# WaldoRevC.net
KiCad netlist of a schematic drawn in EAGLE
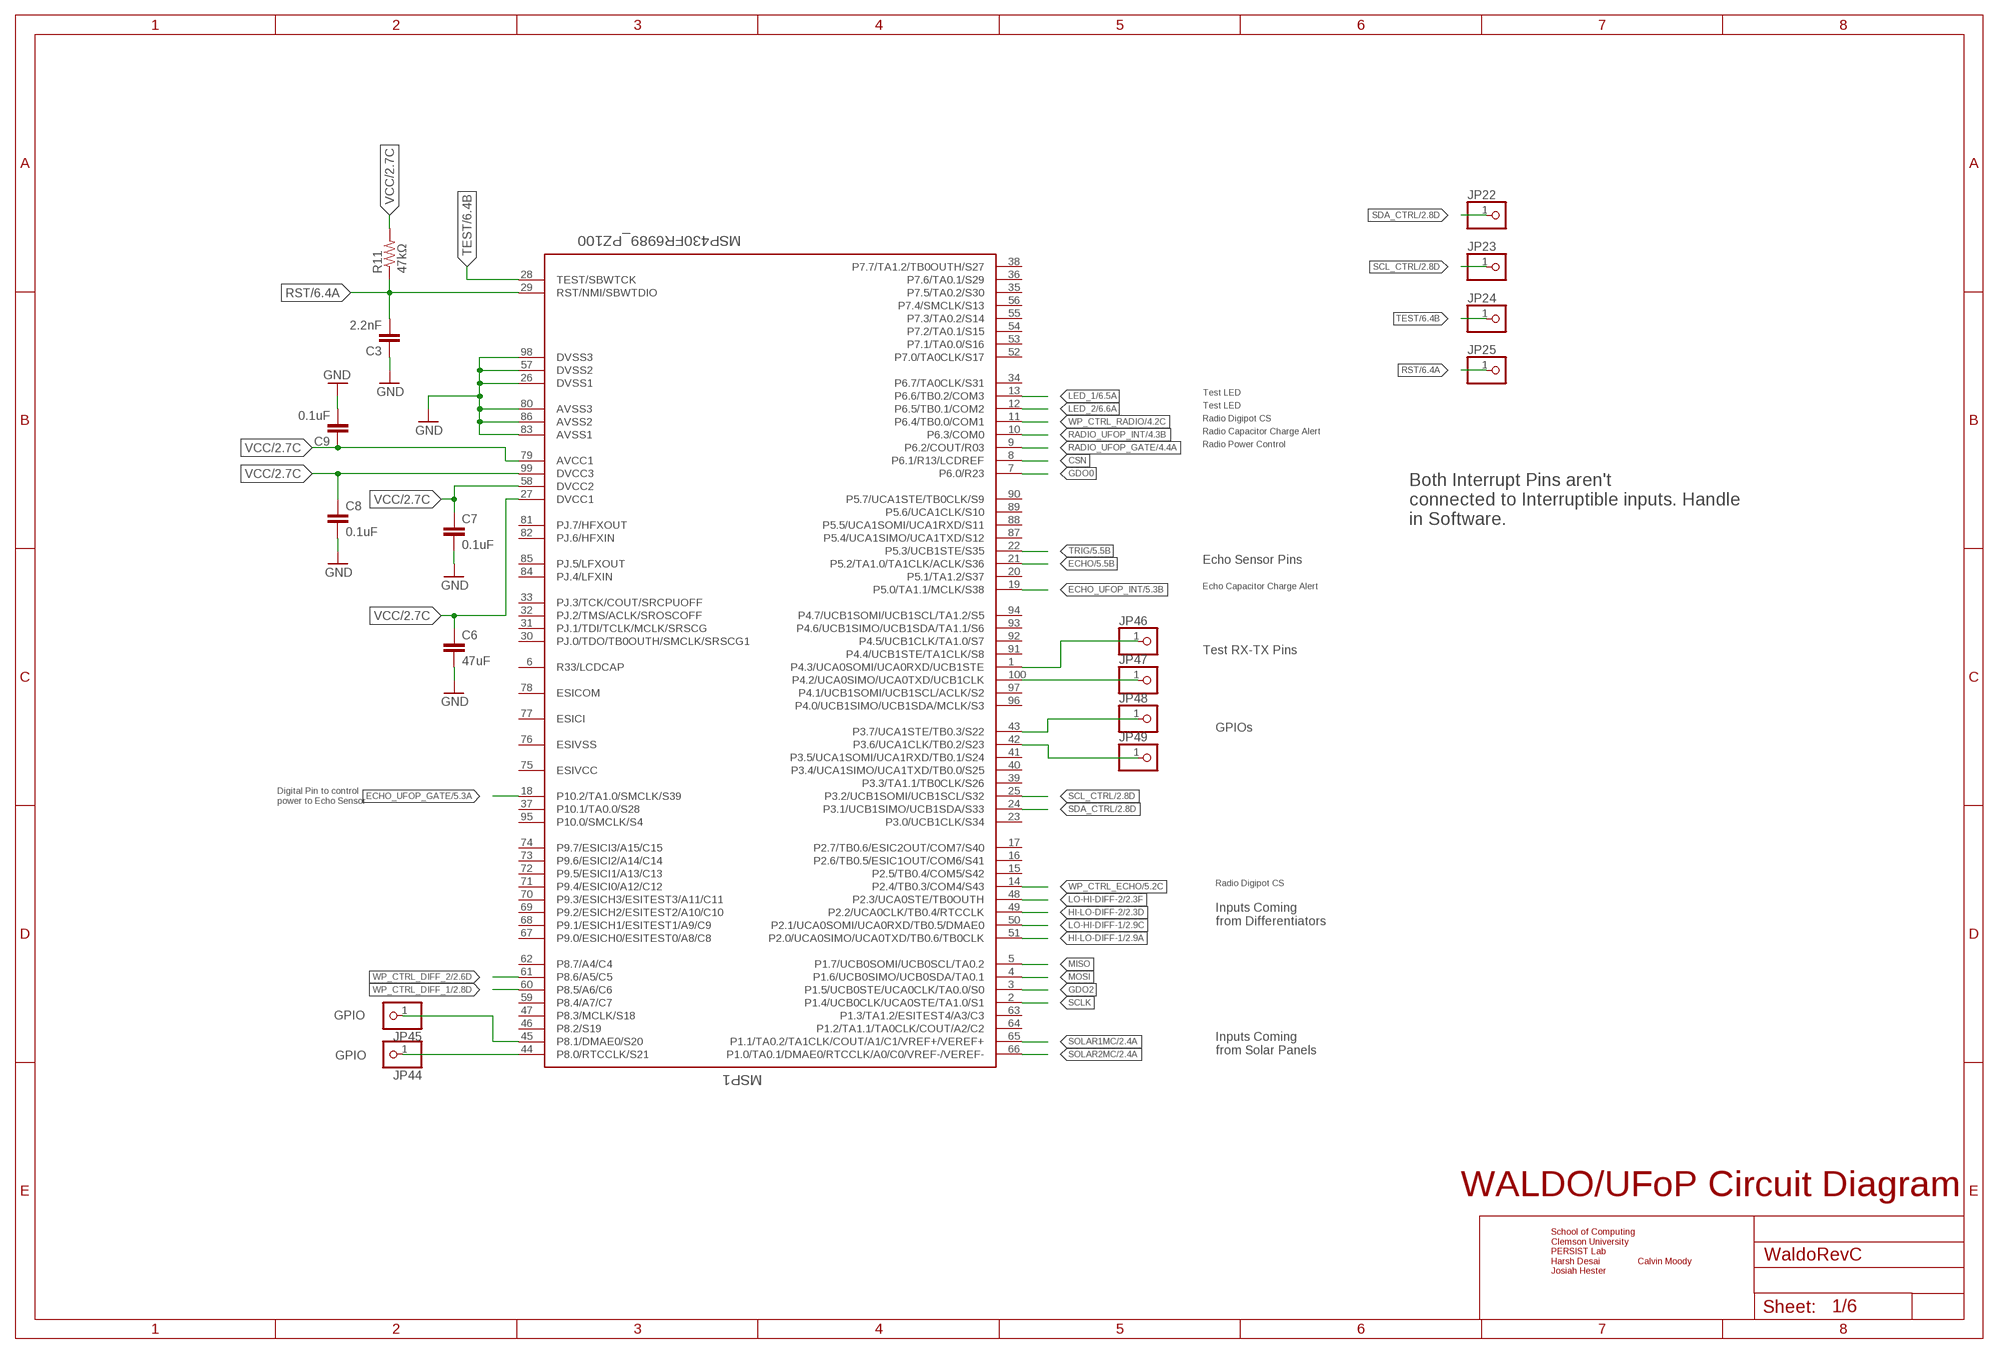
[diagram p0: schematic, sheet 1]
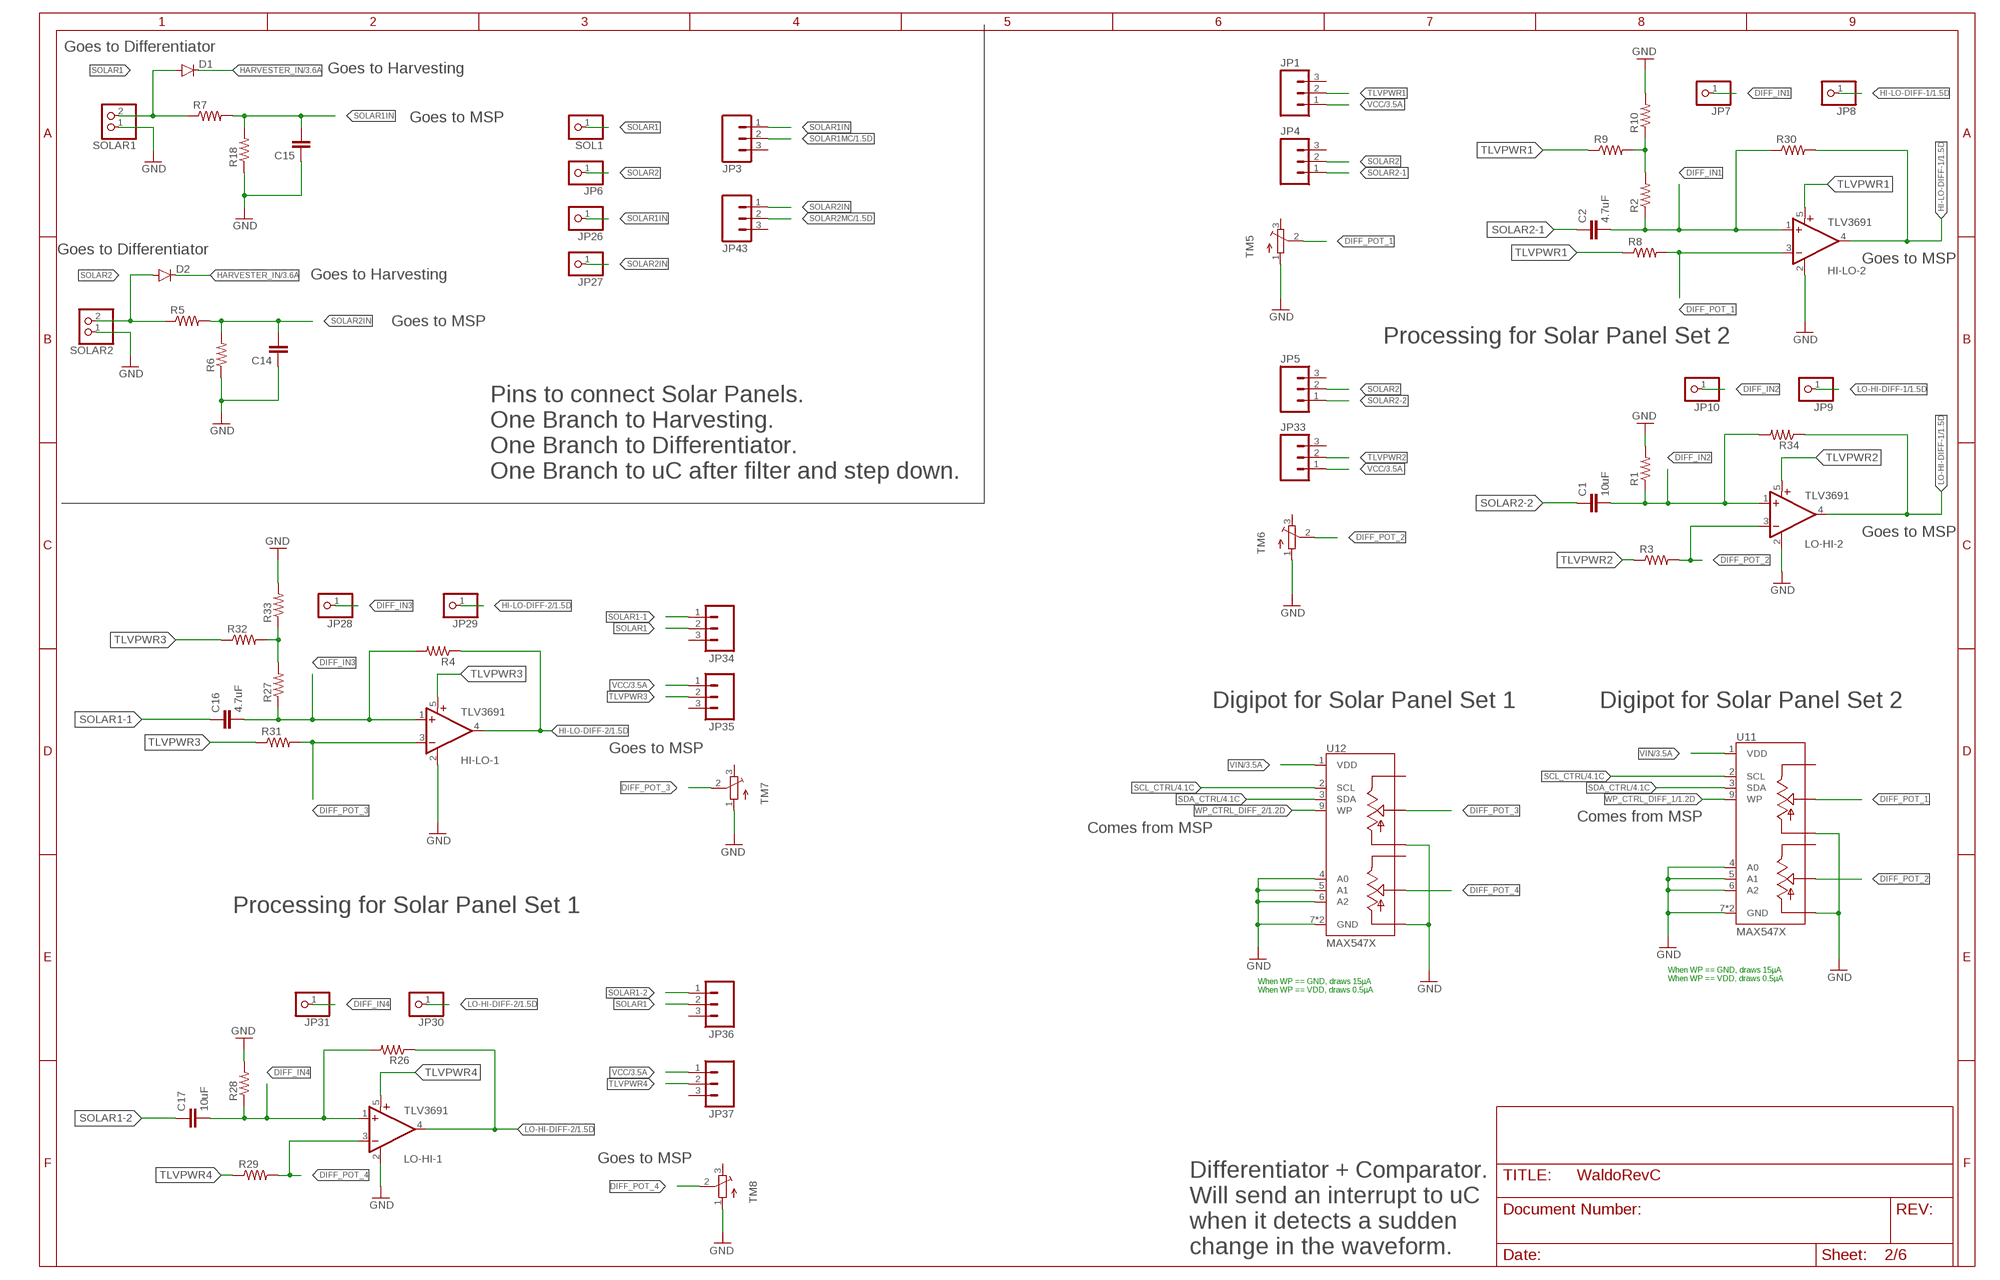
[diagram p1: schematic, sheet 2]
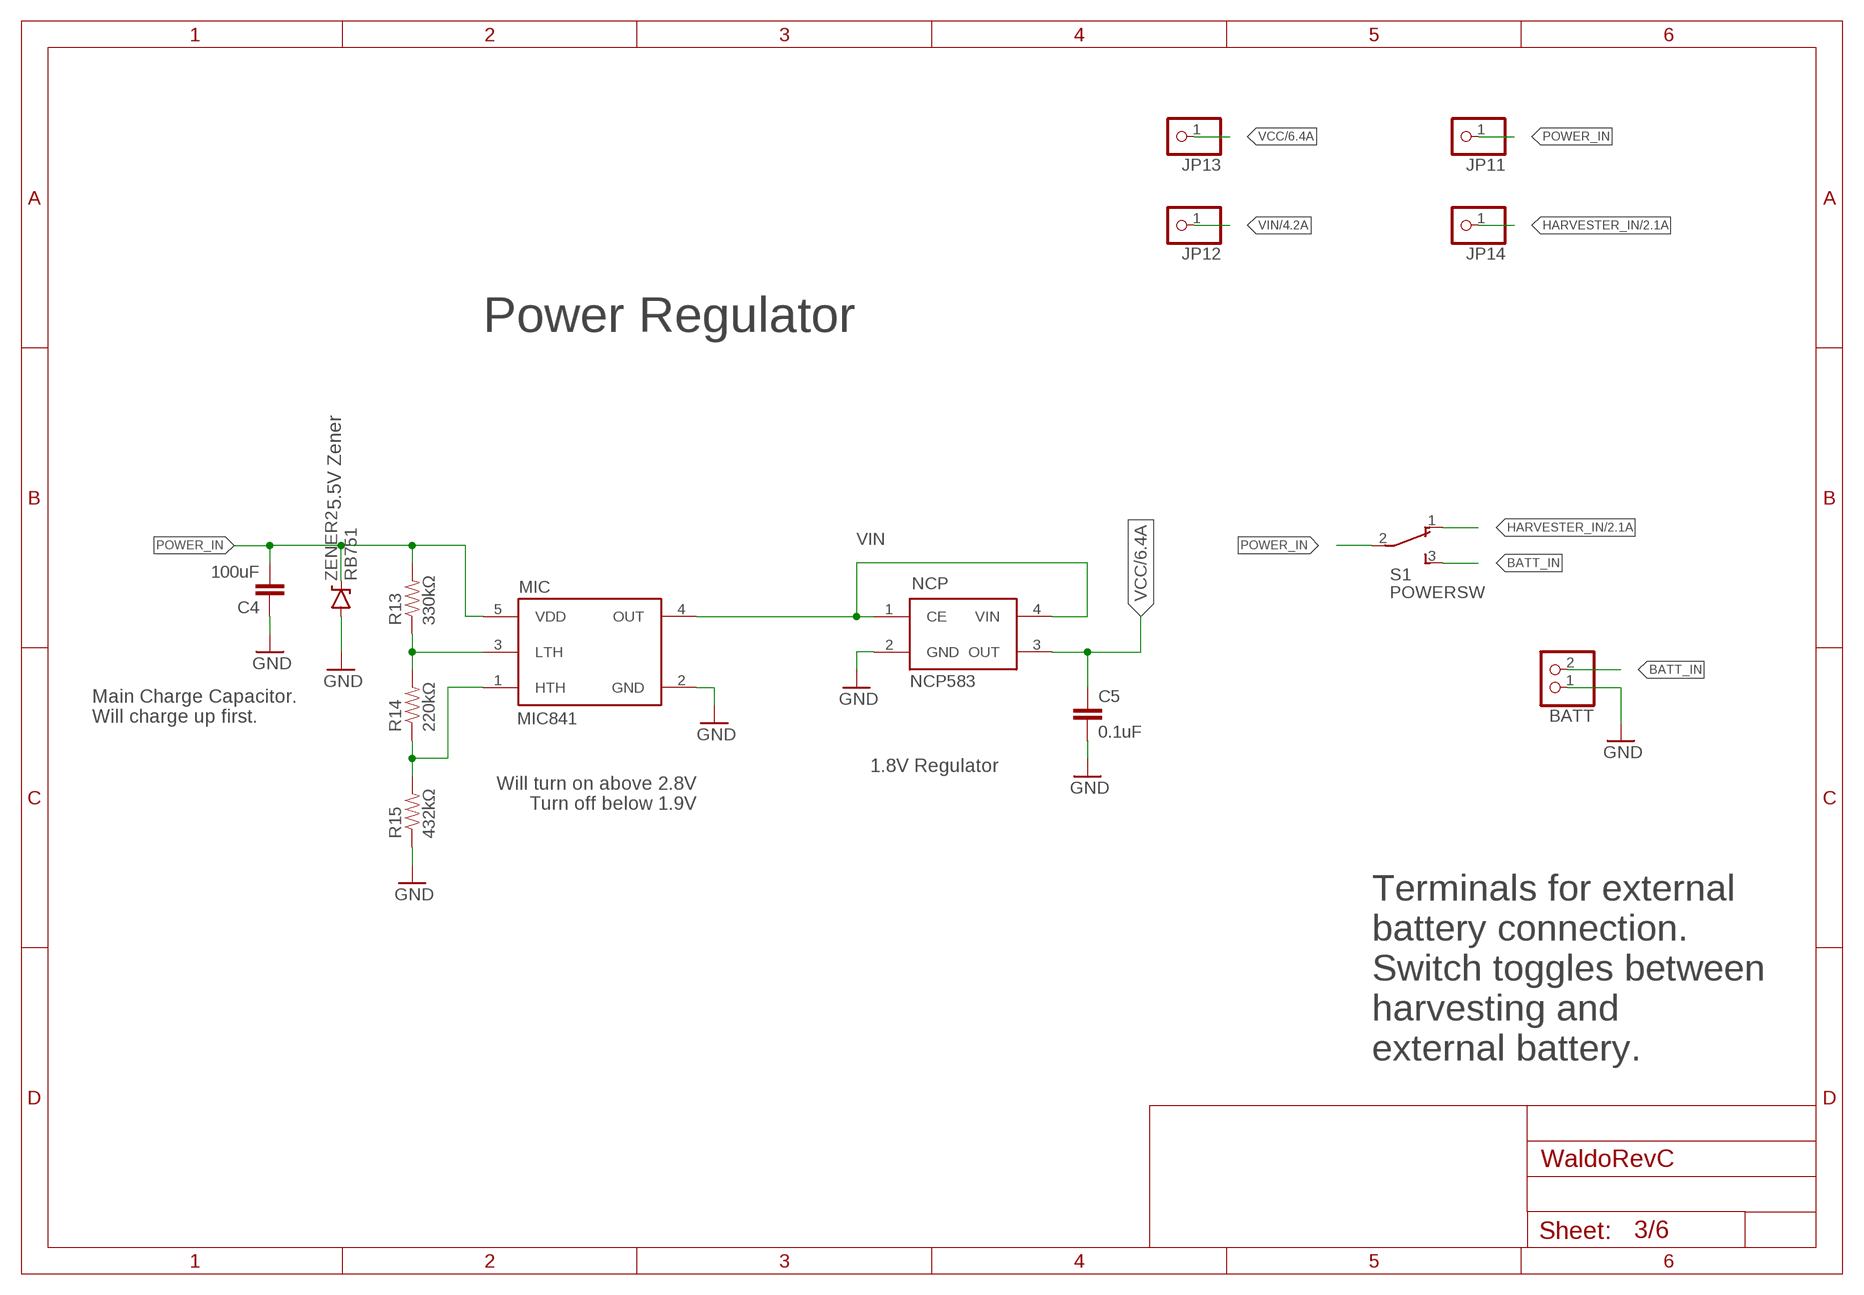
[diagram p2: schematic, sheet 3]
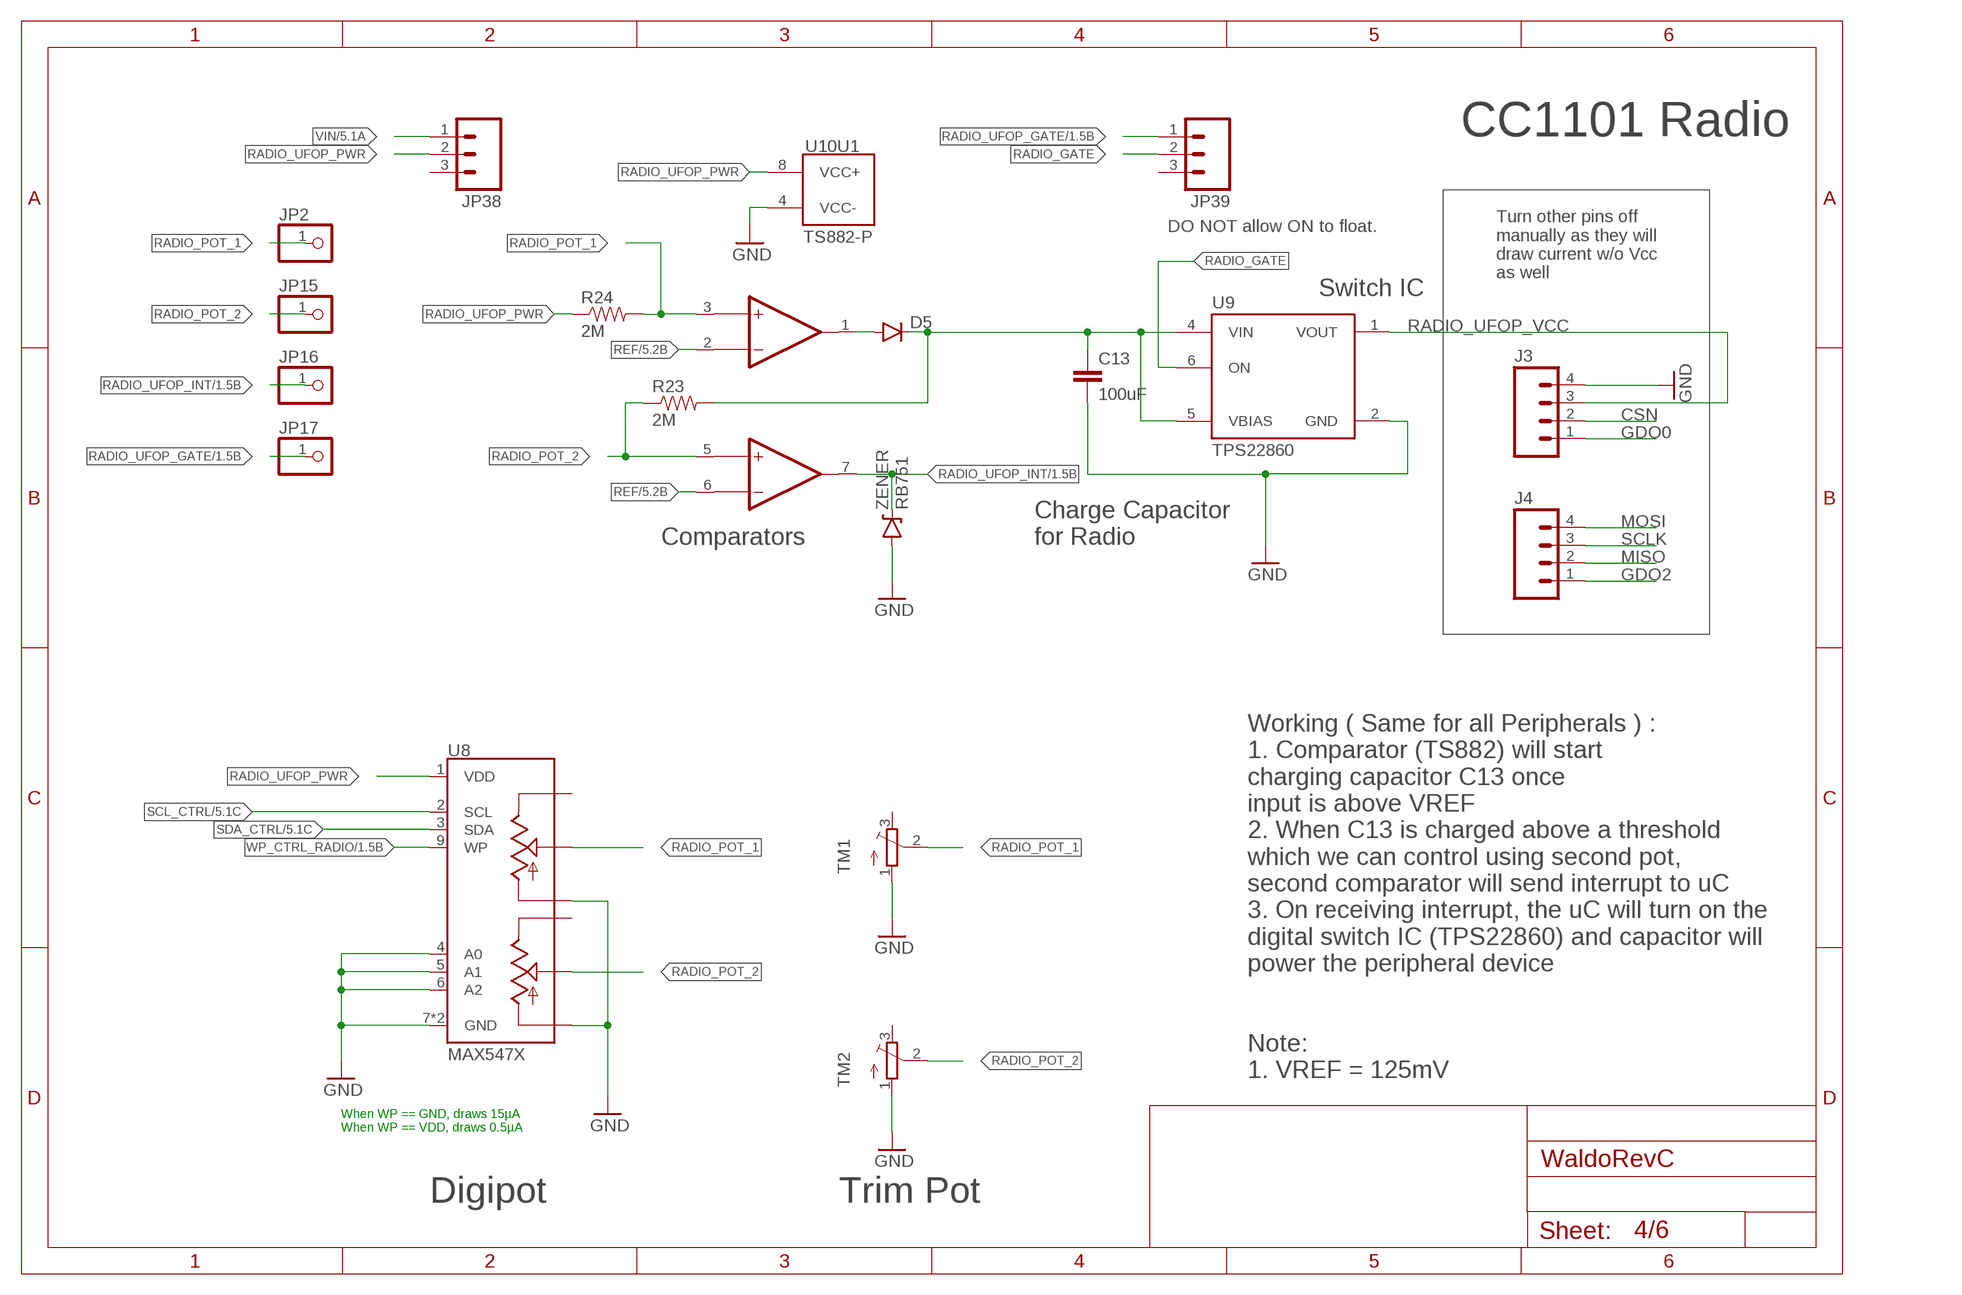
[diagram p3: schematic, sheet 4]
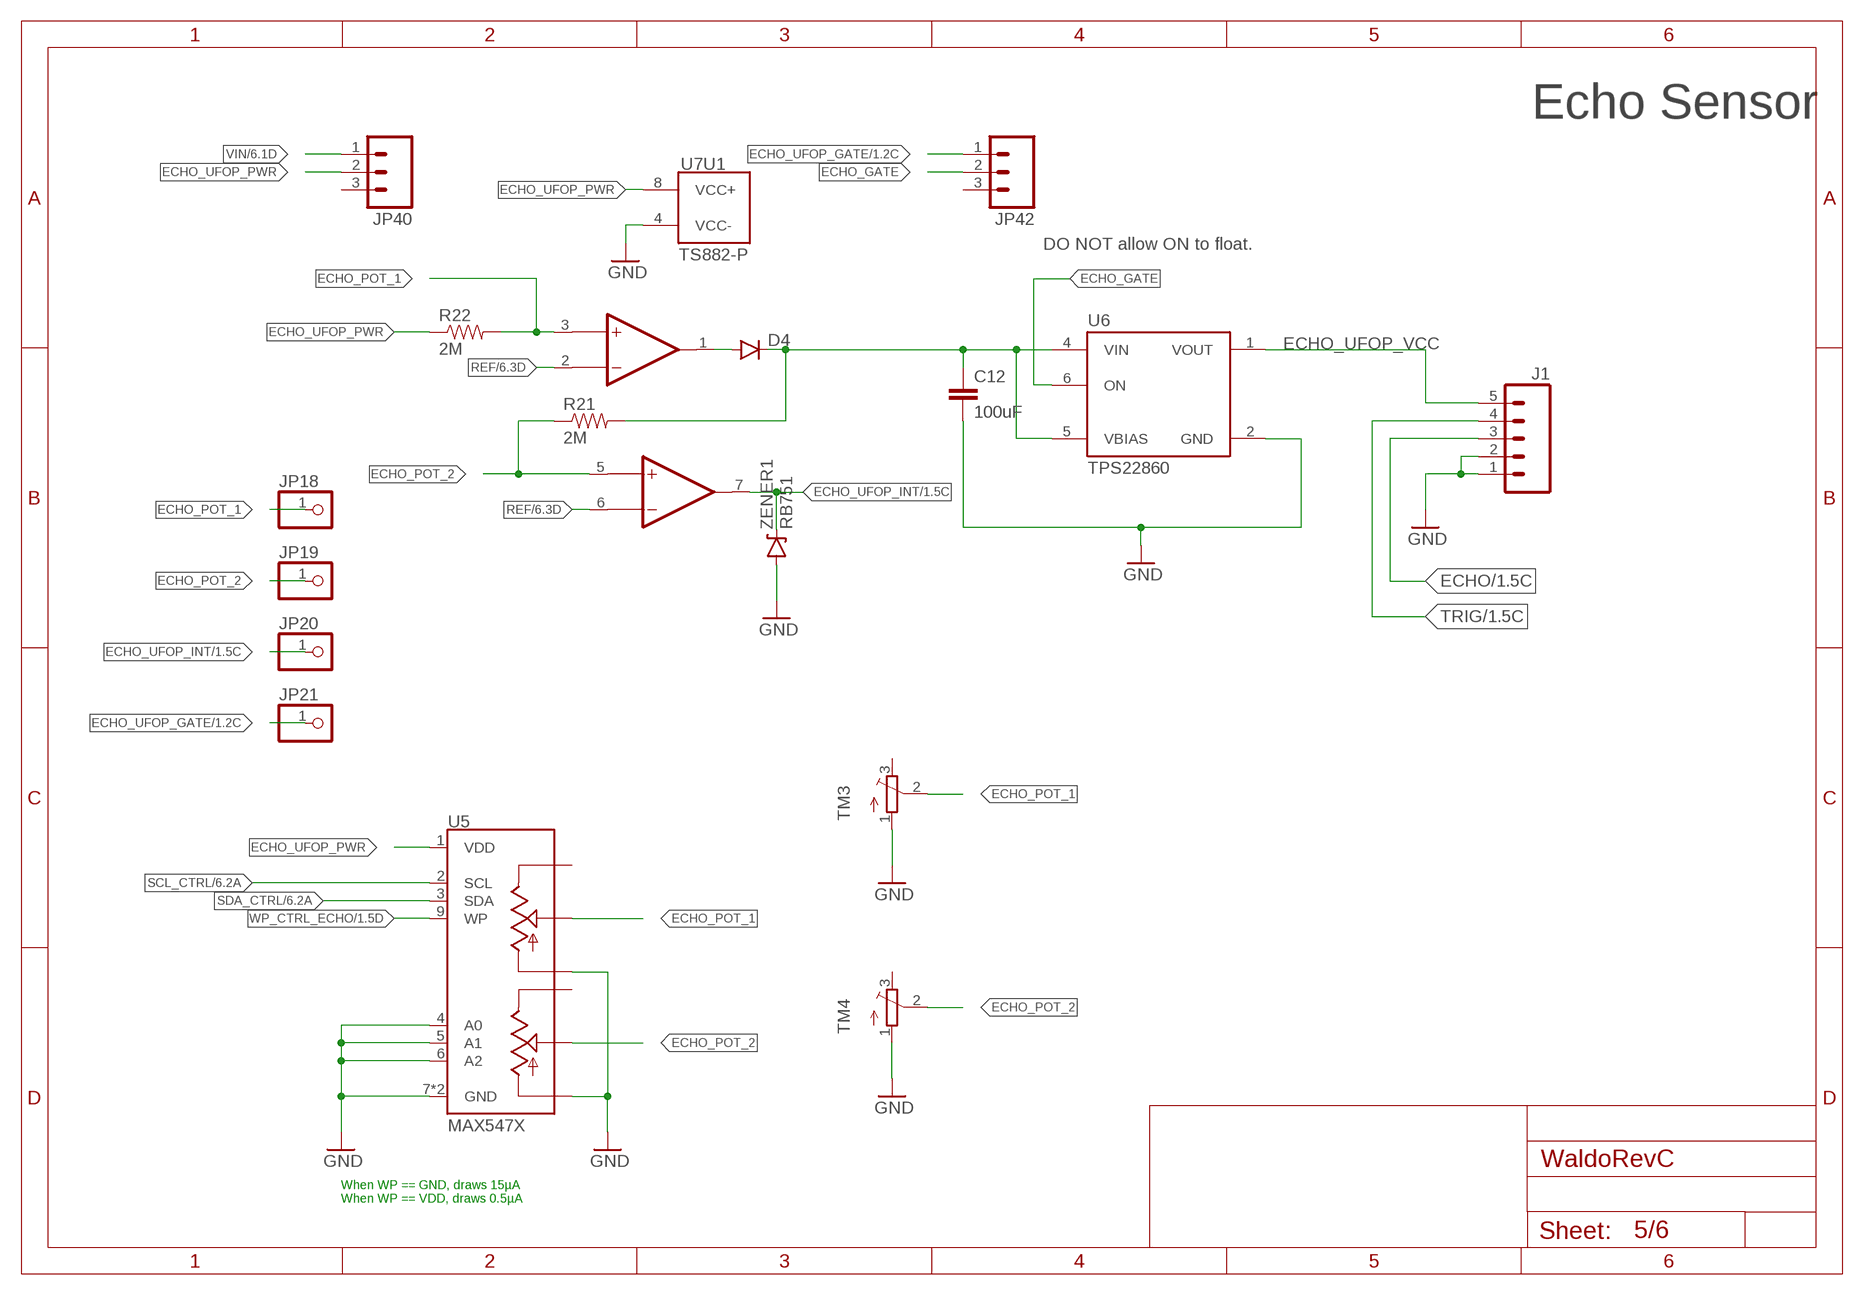
[diagram p4: schematic, sheet 5]
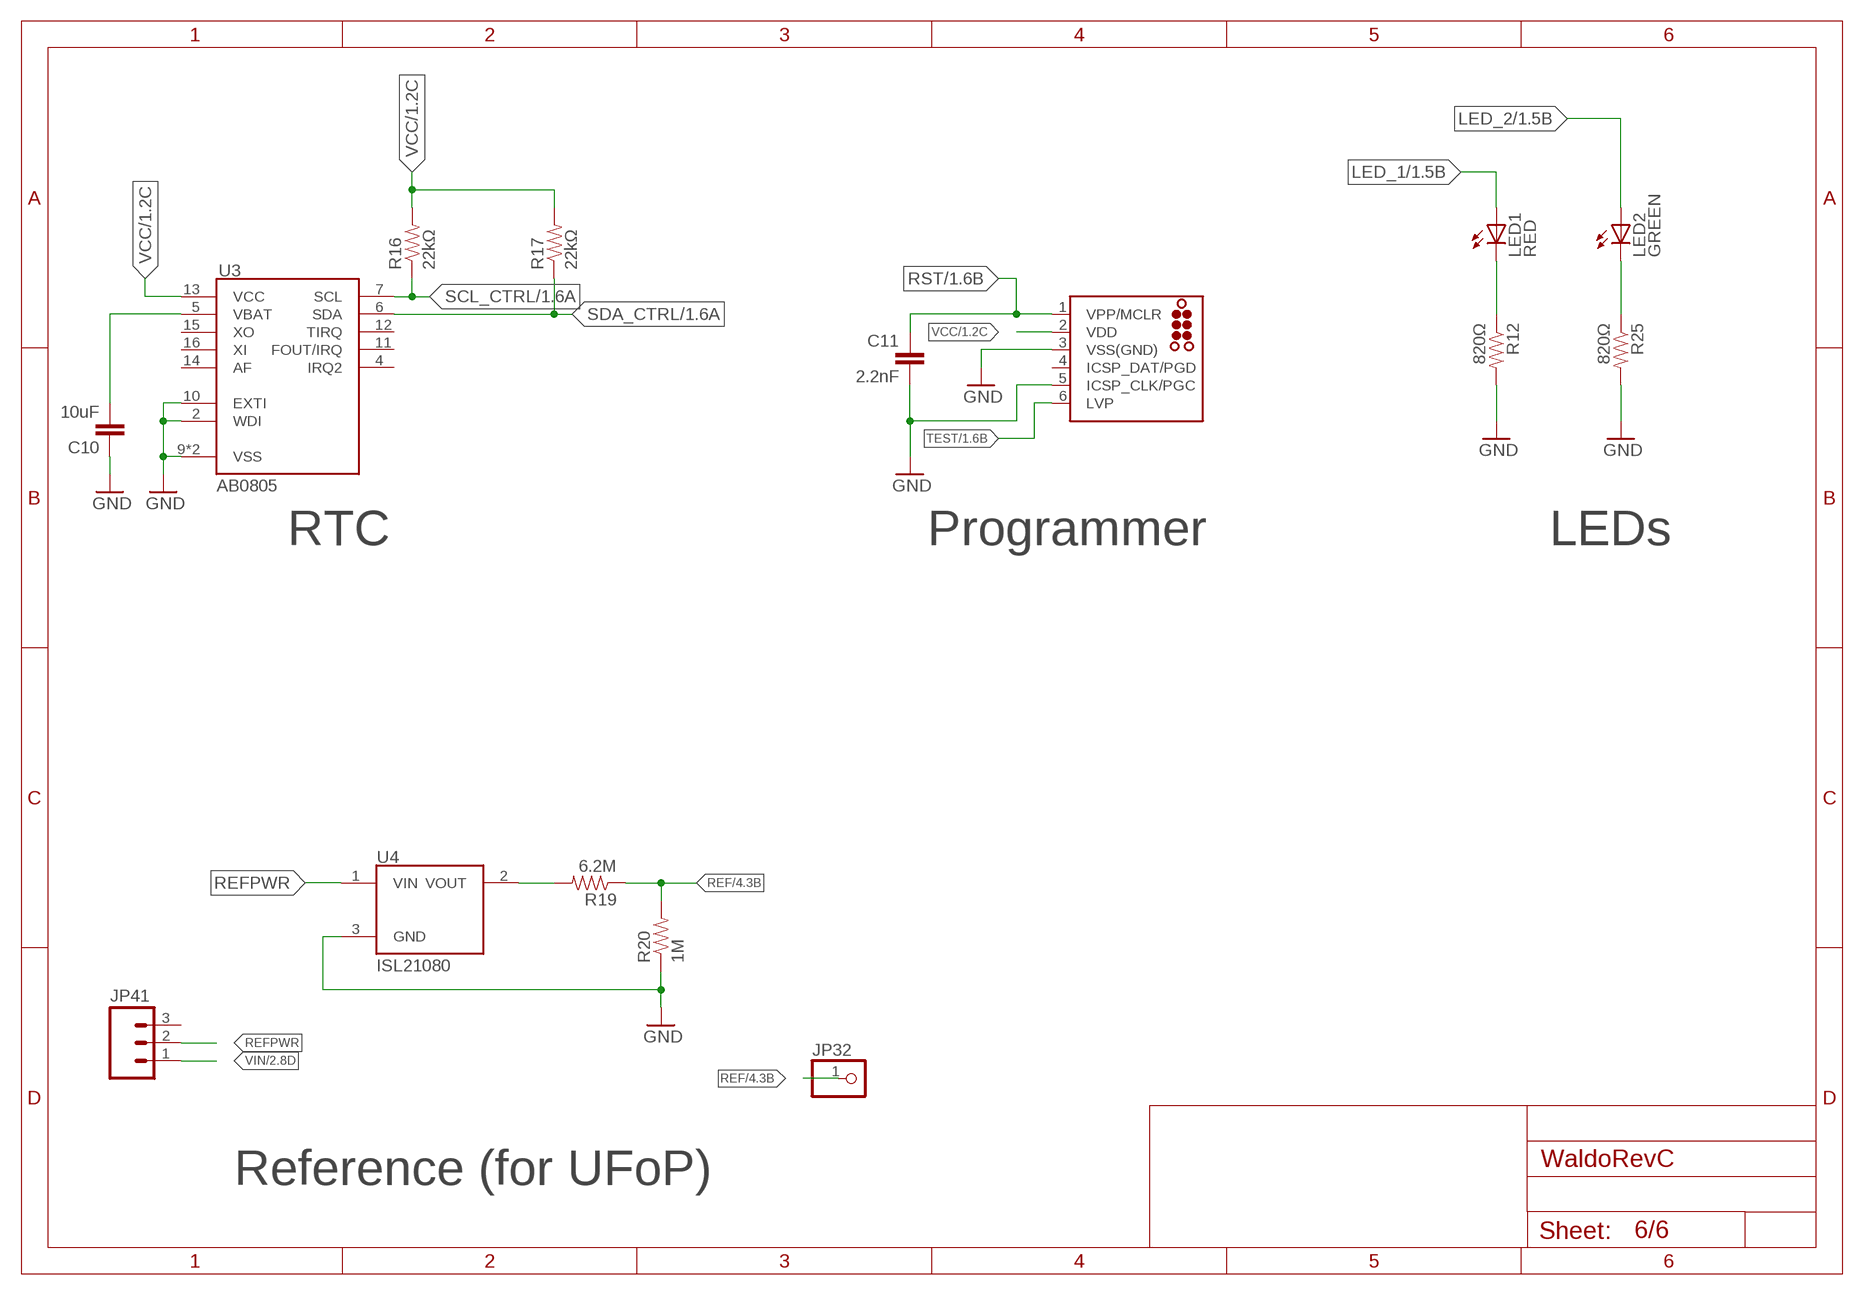
[diagram p5: schematic, sheet 6]

(export (version "E")
  (design (tool "Eeschema 10.0.6"))
  (components
    (comp (ref "C12")
      (value "100uF")
      (footprint "eagle-import:0805")
      (libsource (lib "eagle-import") (part "CAP0805"))
    )
    (comp (ref "D4")
      (value "DIODESOD523")
      (footprint "eagle-import:SOD523")
      (libsource (lib "eagle-import") (part "DIODESOD523"))
    )
    (comp (ref "J1")
      (value "M05PTH")
      (footprint "eagle-import:1X05")
      (libsource (lib "eagle-import") (part "M05PTH"))
    )
    (comp (ref "JP18")
      (value "PINHD-1X1")
      (footprint "eagle-import:1X01")
      (libsource (lib "eagle-import") (part "PINHD-1X1"))
    )
    (comp (ref "JP19")
      (value "PINHD-1X1")
      (footprint "eagle-import:1X01")
      (libsource (lib "eagle-import") (part "PINHD-1X1"))
    )
    (comp (ref "JP20")
      (value "PINHD-1X1")
      (footprint "eagle-import:1X01")
      (libsource (lib "eagle-import") (part "PINHD-1X1"))
    )
    (comp (ref "JP21")
      (value "PINHD-1X1")
      (footprint "eagle-import:1X01")
      (libsource (lib "eagle-import") (part "PINHD-1X1"))
    )
    (comp (ref "JP40")
      (value "M03")
      (footprint "eagle-import:1X03-1.27MM")
      (libsource (lib "eagle-import") (part "M03"))
    )
    (comp (ref "JP42")
      (value "M03")
      (footprint "eagle-import:1X03-1.27MM")
      (libsource (lib "eagle-import") (part "M03"))
    )
    (comp (ref "R21")
      (value "2M")
      (footprint "eagle-import:0805")
      (libsource (lib "eagle-import") (part "RESISTOR0805-RES"))
    )
    (comp (ref "R22")
      (value "2M")
      (footprint "eagle-import:0805")
      (libsource (lib "eagle-import") (part "RESISTOR0805-RES"))
    )
    (comp (ref "TM3")
      (value "TRIMPOTTC33X")
      (footprint "eagle-import:TC33X")
      (libsource (lib "eagle-import") (part "TRIMPOTTC33X"))
    )
    (comp (ref "TM4")
      (value "TRIMPOTTC33X")
      (footprint "eagle-import:TC33X")
      (libsource (lib "eagle-import") (part "TRIMPOTTC33X"))
    )
    (comp (ref "U5")
      (value "MAX547X")
      (footprint "eagle-import:QFN16")
      (libsource (lib "eagle-import") (part "MAX547X"))
    )
    (comp (ref "U6")
      (value "TPS22860")
      (footprint "eagle-import:TSOT23-6")
      (libsource (lib "eagle-import") (part "TPS22860"))
    )
    (comp (ref "U7")
      (value "TS882-P")
      (footprint "eagle-import:UDFN8")
      (fields (field (name "DIGIKEY") "497-14073-1-ND"))
      (libsource (lib "eagle-import") (part "TS882-P"))
    )
    (comp (ref "ZENER1")
      (value "RB751")
      (footprint "eagle-import:SOD-523")
      (libsource (lib "eagle-import") (part "DIODE-ZENER"))
    )
    (comp (ref "C3")
      (value "2.2nF")
      (footprint "eagle-import:0805")
      (libsource (lib "eagle-import") (part "CAP0805"))
    )
    (comp (ref "C6")
      (value "47uF")
      (footprint "eagle-import:0805")
      (libsource (lib "eagle-import") (part "CAP0805"))
    )
    (comp (ref "C7")
      (value "0.1uF")
      (footprint "eagle-import:0805")
      (libsource (lib "eagle-import") (part "CAP0805"))
    )
    (comp (ref "C8")
      (value "0.1uF")
      (footprint "eagle-import:0805")
      (libsource (lib "eagle-import") (part "CAP0805"))
    )
    (comp (ref "C9")
      (value "0.1uF")
      (footprint "eagle-import:0805")
      (libsource (lib "eagle-import") (part "CAP0805"))
    )
    (comp (ref "JP22")
      (value "PINHD-1X1")
      (footprint "eagle-import:1X01")
      (libsource (lib "eagle-import") (part "PINHD-1X1"))
    )
    (comp (ref "JP23")
      (value "PINHD-1X1")
      (footprint "eagle-import:1X01")
      (libsource (lib "eagle-import") (part "PINHD-1X1"))
    )
    (comp (ref "JP24")
      (value "PINHD-1X1")
      (footprint "eagle-import:1X01")
      (libsource (lib "eagle-import") (part "PINHD-1X1"))
    )
    (comp (ref "JP25")
      (value "PINHD-1X1")
      (footprint "eagle-import:1X01")
      (libsource (lib "eagle-import") (part "PINHD-1X1"))
    )
    (comp (ref "JP44")
      (value "PINHD-1X1")
      (footprint "eagle-import:1X01")
      (libsource (lib "eagle-import") (part "PINHD-1X1"))
    )
    (comp (ref "JP45")
      (value "PINHD-1X1")
      (footprint "eagle-import:1X01")
      (libsource (lib "eagle-import") (part "PINHD-1X1"))
    )
    (comp (ref "JP46")
      (value "PINHD-1X1")
      (footprint "eagle-import:1X01")
      (libsource (lib "eagle-import") (part "PINHD-1X1"))
    )
    (comp (ref "JP47")
      (value "PINHD-1X1")
      (footprint "eagle-import:1X01")
      (libsource (lib "eagle-import") (part "PINHD-1X1"))
    )
    (comp (ref "JP48")
      (value "PINHD-1X1")
      (footprint "eagle-import:1X01")
      (libsource (lib "eagle-import") (part "PINHD-1X1"))
    )
    (comp (ref "JP49")
      (value "PINHD-1X1")
      (footprint "eagle-import:1X01")
      (libsource (lib "eagle-import") (part "PINHD-1X1"))
    )
    (comp (ref "MSP1")
      (value "MSP430FR6989_PZ100")
      (footprint "eagle-import:PZ100")
      (libsource (lib "eagle-import") (part "MSP430FR6989_PZ100"))
    )
    (comp (ref "R11")
      (value "47kΩ")
      (footprint "eagle-import:0805")
      (libsource (lib "eagle-import") (part "RESISTOR0805-RES"))
    )
    (comp (ref "C1")
      (value "10uF")
      (footprint "eagle-import:0805")
      (libsource (lib "eagle-import") (part "CAP0805"))
    )
    (comp (ref "C2")
      (value "4.7uF")
      (footprint "eagle-import:0805")
      (libsource (lib "eagle-import") (part "CAP0805"))
    )
    (comp (ref "C14")
      (value "CAP0805")
      (footprint "eagle-import:0805")
      (libsource (lib "eagle-import") (part "CAP0805"))
    )
    (comp (ref "C15")
      (value "CAP0805")
      (footprint "eagle-import:0805")
      (libsource (lib "eagle-import") (part "CAP0805"))
    )
    (comp (ref "C16")
      (value "4.7uF")
      (footprint "eagle-import:0805")
      (libsource (lib "eagle-import") (part "CAP0805"))
    )
    (comp (ref "C17")
      (value "10uF")
      (footprint "eagle-import:0805")
      (libsource (lib "eagle-import") (part "CAP0805"))
    )
    (comp (ref "D1")
      (value "DIODESOD523")
      (footprint "eagle-import:SOD523")
      (libsource (lib "eagle-import") (part "DIODESOD523"))
    )
    (comp (ref "D2")
      (value "DIODESOD523")
      (footprint "eagle-import:SOD523")
      (libsource (lib "eagle-import") (part "DIODESOD523"))
    )
    (comp (ref "HI-LO-1")
      (value "TLV3691")
      (footprint "eagle-import:SC70-5")
      (libsource (lib "eagle-import") (part "TLV3691"))
    )
    (comp (ref "HI-LO-2")
      (value "TLV3691")
      (footprint "eagle-import:SC70-5")
      (libsource (lib "eagle-import") (part "TLV3691"))
    )
    (comp (ref "JP1")
      (value "M03")
      (footprint "eagle-import:1X03-1.27MM")
      (libsource (lib "eagle-import") (part "M03"))
    )
    (comp (ref "JP3")
      (value "M03")
      (footprint "eagle-import:1X03-1.27MM")
      (libsource (lib "eagle-import") (part "M03"))
    )
    (comp (ref "JP4")
      (value "M03")
      (footprint "eagle-import:1X03-1.27MM")
      (libsource (lib "eagle-import") (part "M03"))
    )
    (comp (ref "JP5")
      (value "M03")
      (footprint "eagle-import:1X03-1.27MM")
      (libsource (lib "eagle-import") (part "M03"))
    )
    (comp (ref "JP6")
      (value "PINHD-1X1")
      (footprint "eagle-import:1X01")
      (libsource (lib "eagle-import") (part "PINHD-1X1"))
    )
    (comp (ref "JP7")
      (value "PINHD-1X1")
      (footprint "eagle-import:1X01")
      (libsource (lib "eagle-import") (part "PINHD-1X1"))
    )
    (comp (ref "JP8")
      (value "PINHD-1X1")
      (footprint "eagle-import:1X01")
      (libsource (lib "eagle-import") (part "PINHD-1X1"))
    )
    (comp (ref "JP9")
      (value "PINHD-1X1")
      (footprint "eagle-import:1X01")
      (libsource (lib "eagle-import") (part "PINHD-1X1"))
    )
    (comp (ref "JP10")
      (value "PINHD-1X1")
      (footprint "eagle-import:1X01")
      (libsource (lib "eagle-import") (part "PINHD-1X1"))
    )
    (comp (ref "JP26")
      (value "PINHD-1X1")
      (footprint "eagle-import:1X01")
      (libsource (lib "eagle-import") (part "PINHD-1X1"))
    )
    (comp (ref "JP27")
      (value "PINHD-1X1")
      (footprint "eagle-import:1X01")
      (libsource (lib "eagle-import") (part "PINHD-1X1"))
    )
    (comp (ref "JP28")
      (value "PINHD-1X1")
      (footprint "eagle-import:1X01")
      (libsource (lib "eagle-import") (part "PINHD-1X1"))
    )
    (comp (ref "JP29")
      (value "PINHD-1X1")
      (footprint "eagle-import:1X01")
      (libsource (lib "eagle-import") (part "PINHD-1X1"))
    )
    (comp (ref "JP30")
      (value "PINHD-1X1")
      (footprint "eagle-import:1X01")
      (libsource (lib "eagle-import") (part "PINHD-1X1"))
    )
    (comp (ref "JP31")
      (value "PINHD-1X1")
      (footprint "eagle-import:1X01")
      (libsource (lib "eagle-import") (part "PINHD-1X1"))
    )
    (comp (ref "JP33")
      (value "M03")
      (footprint "eagle-import:1X03-1.27MM")
      (libsource (lib "eagle-import") (part "M03"))
    )
    (comp (ref "JP34")
      (value "M03")
      (footprint "eagle-import:1X03-1.27MM")
      (libsource (lib "eagle-import") (part "M03"))
    )
    (comp (ref "JP35")
      (value "M03")
      (footprint "eagle-import:1X03-1.27MM")
      (libsource (lib "eagle-import") (part "M03"))
    )
    (comp (ref "JP36")
      (value "M03")
      (footprint "eagle-import:1X03-1.27MM")
      (libsource (lib "eagle-import") (part "M03"))
    )
    (comp (ref "JP37")
      (value "M03")
      (footprint "eagle-import:1X03-1.27MM")
      (libsource (lib "eagle-import") (part "M03"))
    )
    (comp (ref "JP43")
      (value "M03")
      (footprint "eagle-import:1X03-1.27MM")
      (libsource (lib "eagle-import") (part "M03"))
    )
    (comp (ref "LO-HI-1")
      (value "TLV3691")
      (footprint "eagle-import:SC70-5")
      (libsource (lib "eagle-import") (part "TLV3691"))
    )
    (comp (ref "LO-HI-2")
      (value "TLV3691")
      (footprint "eagle-import:SC70-5")
      (libsource (lib "eagle-import") (part "TLV3691"))
    )
    (comp (ref "R1")
      (value "RESISTOR0805-RES")
      (footprint "eagle-import:0805")
      (libsource (lib "eagle-import") (part "RESISTOR0805-RES"))
    )
    (comp (ref "R2")
      (value "RESISTOR0805-RES")
      (footprint "eagle-import:0805")
      (libsource (lib "eagle-import") (part "RESISTOR0805-RES"))
    )
    (comp (ref "R3")
      (value "RESISTOR0805-RES")
      (footprint "eagle-import:0805")
      (libsource (lib "eagle-import") (part "RESISTOR0805-RES"))
    )
    (comp (ref "R4")
      (value "RESISTOR0805-RES")
      (footprint "eagle-import:0805")
      (libsource (lib "eagle-import") (part "RESISTOR0805-RES"))
    )
    (comp (ref "R5")
      (value "RESISTOR0805-RES")
      (footprint "eagle-import:0805")
      (libsource (lib "eagle-import") (part "RESISTOR0805-RES"))
    )
    (comp (ref "R6")
      (value "RESISTOR0805-RES")
      (footprint "eagle-import:0805")
      (libsource (lib "eagle-import") (part "RESISTOR0805-RES"))
    )
    (comp (ref "R7")
      (value "RESISTOR0805-RES")
      (footprint "eagle-import:0805")
      (libsource (lib "eagle-import") (part "RESISTOR0805-RES"))
    )
    (comp (ref "R8")
      (value "RESISTOR0805-RES")
      (footprint "eagle-import:0805")
      (libsource (lib "eagle-import") (part "RESISTOR0805-RES"))
    )
    (comp (ref "R9")
      (value "RESISTOR0805-RES")
      (footprint "eagle-import:0805")
      (libsource (lib "eagle-import") (part "RESISTOR0805-RES"))
    )
    (comp (ref "R10")
      (value "RESISTOR0805-RES")
      (footprint "eagle-import:0805")
      (libsource (lib "eagle-import") (part "RESISTOR0805-RES"))
    )
    (comp (ref "R18")
      (value "RESISTOR0805-RES")
      (footprint "eagle-import:0805")
      (libsource (lib "eagle-import") (part "RESISTOR0805-RES"))
    )
    (comp (ref "R26")
      (value "RESISTOR0805-RES")
      (footprint "eagle-import:0805")
      (libsource (lib "eagle-import") (part "RESISTOR0805-RES"))
    )
    (comp (ref "R27")
      (value "RESISTOR0805-RES")
      (footprint "eagle-import:0805")
      (libsource (lib "eagle-import") (part "RESISTOR0805-RES"))
    )
    (comp (ref "R28")
      (value "RESISTOR0805-RES")
      (footprint "eagle-import:0805")
      (libsource (lib "eagle-import") (part "RESISTOR0805-RES"))
    )
    (comp (ref "R29")
      (value "RESISTOR0805-RES")
      (footprint "eagle-import:0805")
      (libsource (lib "eagle-import") (part "RESISTOR0805-RES"))
    )
    (comp (ref "R30")
      (value "RESISTOR0805-RES")
      (footprint "eagle-import:0805")
      (libsource (lib "eagle-import") (part "RESISTOR0805-RES"))
    )
    (comp (ref "R31")
      (value "RESISTOR0805-RES")
      (footprint "eagle-import:0805")
      (libsource (lib "eagle-import") (part "RESISTOR0805-RES"))
    )
    (comp (ref "R32")
      (value "RESISTOR0805-RES")
      (footprint "eagle-import:0805")
      (libsource (lib "eagle-import") (part "RESISTOR0805-RES"))
    )
    (comp (ref "R33")
      (value "RESISTOR0805-RES")
      (footprint "eagle-import:0805")
      (libsource (lib "eagle-import") (part "RESISTOR0805-RES"))
    )
    (comp (ref "R34")
      (value "RESISTOR0805-RES")
      (footprint "eagle-import:0805")
      (libsource (lib "eagle-import") (part "RESISTOR0805-RES"))
    )
    (comp (ref "SOL1")
      (value "PINHD-1X1")
      (footprint "eagle-import:1X01")
      (libsource (lib "eagle-import") (part "PINHD-1X1"))
    )
    (comp (ref "SOLAR1")
      (value "PINHD-1X2")
      (footprint "eagle-import:1X02")
      (libsource (lib "eagle-import") (part "PINHD-1X2"))
    )
    (comp (ref "SOLAR2")
      (value "PINHD-1X2")
      (footprint "eagle-import:1X02")
      (libsource (lib "eagle-import") (part "PINHD-1X2"))
    )
    (comp (ref "TM5")
      (value "TRIMPOTTC33X")
      (footprint "eagle-import:TC33X")
      (libsource (lib "eagle-import") (part "TRIMPOTTC33X"))
    )
    (comp (ref "TM6")
      (value "TRIMPOTTC33X")
      (footprint "eagle-import:TC33X")
      (libsource (lib "eagle-import") (part "TRIMPOTTC33X"))
    )
    (comp (ref "TM7")
      (value "TRIMPOTTC33X")
      (footprint "eagle-import:TC33X")
      (libsource (lib "eagle-import") (part "TRIMPOTTC33X"))
    )
    (comp (ref "TM8")
      (value "TRIMPOTTC33X")
      (footprint "eagle-import:TC33X")
      (libsource (lib "eagle-import") (part "TRIMPOTTC33X"))
    )
    (comp (ref "U11")
      (value "MAX547X")
      (footprint "eagle-import:QFN16")
      (libsource (lib "eagle-import") (part "MAX547X"))
    )
    (comp (ref "U12")
      (value "MAX547X")
      (footprint "eagle-import:QFN16")
      (libsource (lib "eagle-import") (part "MAX547X"))
    )
    (comp (ref "C10")
      (value "10uF")
      (footprint "eagle-import:0805")
      (libsource (lib "eagle-import") (part "CAP0805"))
    )
    (comp (ref "C11")
      (value "2.2nF")
      (footprint "eagle-import:0805")
      (libsource (lib "eagle-import") (part "CAP0805"))
    )
    (comp (ref "J2")
      (value "TC2030-MCP-NL")
      (footprint "eagle-import:TC2030-MCP-NL")
      (libsource (lib "eagle-import") (part "TC2030-MCP-NL"))
    )
    (comp (ref "JP32")
      (value "PINHD-1X1")
      (footprint "eagle-import:1X01")
      (libsource (lib "eagle-import") (part "PINHD-1X1"))
    )
    (comp (ref "JP41")
      (value "M03")
      (footprint "eagle-import:1X03-1.27MM")
      (libsource (lib "eagle-import") (part "M03"))
    )
    (comp (ref "LED1")
      (value "RED")
      (footprint "eagle-import:CHIP-LED0805")
      (libsource (lib "eagle-import") (part "LEDCHIP-LED0805"))
    )
    (comp (ref "LED2")
      (value "GREEN")
      (footprint "eagle-import:CHIP-LED0805")
      (libsource (lib "eagle-import") (part "LEDCHIP-LED0805"))
    )
    (comp (ref "R12")
      (value "820Ω")
      (footprint "eagle-import:0805")
      (libsource (lib "eagle-import") (part "RESISTOR0805-RES"))
    )
    (comp (ref "R16")
      (value "22kΩ")
      (footprint "eagle-import:0805")
      (libsource (lib "eagle-import") (part "RESISTOR0805-RES"))
    )
    (comp (ref "R17")
      (value "22kΩ")
      (footprint "eagle-import:0805")
      (libsource (lib "eagle-import") (part "RESISTOR0805-RES"))
    )
    (comp (ref "R19")
      (value "6.2M")
      (footprint "eagle-import:0805")
      (libsource (lib "eagle-import") (part "RESISTOR0805-RES"))
    )
    (comp (ref "R20")
      (value "1M")
      (footprint "eagle-import:0805")
      (libsource (lib "eagle-import") (part "RESISTOR0805-RES"))
    )
    (comp (ref "R25")
      (value "820Ω")
      (footprint "eagle-import:0805")
      (libsource (lib "eagle-import") (part "RESISTOR0805-RES"))
    )
    (comp (ref "U3")
      (value "AB0805")
      (footprint "eagle-import:QFN16")
      (libsource (lib "eagle-import") (part "AB0805"))
    )
    (comp (ref "U4")
      (value "ISL21080")
      (footprint "eagle-import:SOT-23")
      (libsource (lib "eagle-import") (part "ISL21080"))
    )
    (comp (ref "BATT")
      (value "PINHD-1X2")
      (footprint "eagle-import:1X02")
      (libsource (lib "eagle-import") (part "PINHD-1X2"))
    )
    (comp (ref "C4")
      (value "100uF")
      (footprint "eagle-import:0805")
      (libsource (lib "eagle-import") (part "CAP0805"))
    )
    (comp (ref "C5")
      (value "0.1uF")
      (footprint "eagle-import:0805")
      (libsource (lib "eagle-import") (part "CAP0805"))
    )
    (comp (ref "JP11")
      (value "PINHD-1X1")
      (footprint "eagle-import:1X01")
      (libsource (lib "eagle-import") (part "PINHD-1X1"))
    )
    (comp (ref "JP12")
      (value "PINHD-1X1")
      (footprint "eagle-import:1X01")
      (libsource (lib "eagle-import") (part "PINHD-1X1"))
    )
    (comp (ref "JP13")
      (value "PINHD-1X1")
      (footprint "eagle-import:1X01")
      (libsource (lib "eagle-import") (part "PINHD-1X1"))
    )
    (comp (ref "JP14")
      (value "PINHD-1X1")
      (footprint "eagle-import:1X01")
      (libsource (lib "eagle-import") (part "PINHD-1X1"))
    )
    (comp (ref "MIC")
      (value "MIC841")
      (footprint "eagle-import:SC70-5")
      (libsource (lib "eagle-import") (part "MIC841"))
    )
    (comp (ref "NCP")
      (value "NCP583")
      (footprint "eagle-import:SC82-AB_1PRIMARY")
      (libsource (lib "eagle-import") (part "NCP583"))
    )
    (comp (ref "R13")
      (value "330kΩ")
      (footprint "eagle-import:0805")
      (libsource (lib "eagle-import") (part "RESISTOR0805-RES"))
    )
    (comp (ref "R14")
      (value "220kΩ")
      (footprint "eagle-import:0805")
      (libsource (lib "eagle-import") (part "RESISTOR0805-RES"))
    )
    (comp (ref "R15")
      (value "432kΩ")
      (footprint "eagle-import:0805")
      (libsource (lib "eagle-import") (part "RESISTOR0805-RES"))
    )
    (comp (ref "S1")
      (value "POWERSW")
      (footprint "eagle-import:TL3XYO")
      (libsource (lib "eagle-import") (part "POWERSW"))
    )
    (comp (ref "ZENER2")
      (value "RB751")
      (footprint "eagle-import:SOD-523")
      (libsource (lib "eagle-import") (part "DIODE-ZENER"))
    )
    (comp (ref "C13")
      (value "100uF")
      (footprint "eagle-import:0805")
      (libsource (lib "eagle-import") (part "CAP0805"))
    )
    (comp (ref "D5")
      (value "DIODESOD523")
      (footprint "eagle-import:SOD523")
      (libsource (lib "eagle-import") (part "DIODESOD523"))
    )
    (comp (ref "J3")
      (value "M04PTH")
      (footprint "eagle-import:1X04")
      (libsource (lib "eagle-import") (part "M04PTH"))
    )
    (comp (ref "J4")
      (value "M04PTH")
      (footprint "eagle-import:1X04")
      (libsource (lib "eagle-import") (part "M04PTH"))
    )
    (comp (ref "JP2")
      (value "PINHD-1X1")
      (footprint "eagle-import:1X01")
      (libsource (lib "eagle-import") (part "PINHD-1X1"))
    )
    (comp (ref "JP15")
      (value "PINHD-1X1")
      (footprint "eagle-import:1X01")
      (libsource (lib "eagle-import") (part "PINHD-1X1"))
    )
    (comp (ref "JP16")
      (value "PINHD-1X1")
      (footprint "eagle-import:1X01")
      (libsource (lib "eagle-import") (part "PINHD-1X1"))
    )
    (comp (ref "JP17")
      (value "PINHD-1X1")
      (footprint "eagle-import:1X01")
      (libsource (lib "eagle-import") (part "PINHD-1X1"))
    )
    (comp (ref "JP38")
      (value "M03")
      (footprint "eagle-import:1X03-1.27MM")
      (libsource (lib "eagle-import") (part "M03"))
    )
    (comp (ref "JP39")
      (value "M03")
      (footprint "eagle-import:1X03-1.27MM")
      (libsource (lib "eagle-import") (part "M03"))
    )
    (comp (ref "R23")
      (value "2M")
      (footprint "eagle-import:0805")
      (libsource (lib "eagle-import") (part "RESISTOR0805-RES"))
    )
    (comp (ref "R24")
      (value "2M")
      (footprint "eagle-import:0805")
      (libsource (lib "eagle-import") (part "RESISTOR0805-RES"))
    )
    (comp (ref "TM1")
      (value "TRIMPOTTC33X")
      (footprint "eagle-import:TC33X")
      (libsource (lib "eagle-import") (part "TRIMPOTTC33X"))
    )
    (comp (ref "TM2")
      (value "TRIMPOTTC33X")
      (footprint "eagle-import:TC33X")
      (libsource (lib "eagle-import") (part "TRIMPOTTC33X"))
    )
    (comp (ref "U8")
      (value "MAX547X")
      (footprint "eagle-import:QFN16")
      (libsource (lib "eagle-import") (part "MAX547X"))
    )
    (comp (ref "U9")
      (value "TPS22860")
      (footprint "eagle-import:TSOT23-6")
      (libsource (lib "eagle-import") (part "TPS22860"))
    )
    (comp (ref "U10")
      (value "TS882-P")
      (footprint "eagle-import:UDFN8")
      (fields (field (name "DIGIKEY") "497-14073-1-ND"))
      (libsource (lib "eagle-import") (part "TS882-P"))
    )
    (comp (ref "ZENER")
      (value "RB751")
      (footprint "eagle-import:SOD-523")
      (libsource (lib "eagle-import") (part "DIODE-ZENER"))
    )
  )
  (nets
    (net (code "1") (name "BATT_IN") (class "Default")
      (node (ref "BATT") (pin "2") (pinfunction "2_2") (pintype "passive"))
      (node (ref "S1") (pin "3") (pinfunction "S_3") (pintype "passive"))
    )
    (net (code "2") (name "CSN") (class "Default")
      (node (ref "J3") (pin "2") (pinfunction "2_2") (pintype "passive"))
      (node (ref "MSP1") (pin "8") (pinfunction "P6.1/R13/LCDREF_8") (pintype "bidirectional"))
    )
    (net (code "3") (name "DIFF_IN1") (class "Default")
      (node (ref "C2") (pin "2") (pinfunction "2_2") (pintype "passive"))
      (node (ref "HI-LO-2") (pin "1") (pinfunction "+IN_1") (pintype "input"))
      (node (ref "JP7") (pin "1") (pinfunction "1_1") (pintype "passive"))
      (node (ref "R2") (pin "1") (pinfunction "1_1") (pintype "passive"))
      (node (ref "R30") (pin "1") (pinfunction "1_1") (pintype "passive"))
    )
    (net (code "4") (name "DIFF_IN2") (class "Default")
      (node (ref "C1") (pin "2") (pinfunction "2_2") (pintype "passive"))
      (node (ref "JP10") (pin "1") (pinfunction "1_1") (pintype "passive"))
      (node (ref "LO-HI-2") (pin "1") (pinfunction "+IN_1") (pintype "input"))
      (node (ref "R1") (pin "1") (pinfunction "1_1") (pintype "passive"))
      (node (ref "R34") (pin "2") (pinfunction "2_2") (pintype "passive"))
    )
    (net (code "5") (name "DIFF_IN3") (class "Default")
      (node (ref "C16") (pin "2") (pinfunction "2_2") (pintype "passive"))
      (node (ref "HI-LO-1") (pin "1") (pinfunction "+IN_1") (pintype "input"))
      (node (ref "JP28") (pin "1") (pinfunction "1_1") (pintype "passive"))
      (node (ref "R27") (pin "1") (pinfunction "1_1") (pintype "passive"))
      (node (ref "R4") (pin "2") (pinfunction "2_2") (pintype "passive"))
    )
    (net (code "6") (name "DIFF_IN4") (class "Default")
      (node (ref "C17") (pin "2") (pinfunction "2_2") (pintype "passive"))
      (node (ref "JP31") (pin "1") (pinfunction "1_1") (pintype "passive"))
      (node (ref "LO-HI-1") (pin "1") (pinfunction "+IN_1") (pintype "input"))
      (node (ref "R26") (pin "2") (pinfunction "2_2") (pintype "passive"))
      (node (ref "R28") (pin "1") (pinfunction "1_1") (pintype "passive"))
    )
    (net (code "7") (name "DIFF_POT_1") (class "Default")
      (node (ref "HI-LO-2") (pin "3") (pinfunction "-IN_3") (pintype "input"))
      (node (ref "R8") (pin "2") (pinfunction "2_2") (pintype "passive"))
      (node (ref "TM5") (pin "2") (pinfunction "S_2") (pintype "passive"))
      (node (ref "U11") (pin "14") (pinfunction "WA_14") (pintype "passive"))
    )
    (net (code "8") (name "DIFF_POT_2") (class "Default")
      (node (ref "LO-HI-2") (pin "3") (pinfunction "-IN_3") (pintype "input"))
      (node (ref "R3") (pin "2") (pinfunction "2_2") (pintype "passive"))
      (node (ref "TM6") (pin "2") (pinfunction "S_2") (pintype "passive"))
      (node (ref "U11") (pin "11") (pinfunction "WB_11") (pintype "bidirectional"))
    )
    (net (code "9") (name "DIFF_POT_3") (class "Default")
      (node (ref "HI-LO-1") (pin "3") (pinfunction "-IN_3") (pintype "input"))
      (node (ref "R31") (pin "2") (pinfunction "2_2") (pintype "passive"))
      (node (ref "TM7") (pin "2") (pinfunction "S_2") (pintype "passive"))
      (node (ref "U12") (pin "14") (pinfunction "WA_14") (pintype "passive"))
    )
    (net (code "10") (name "DIFF_POT_4") (class "Default")
      (node (ref "LO-HI-1") (pin "3") (pinfunction "-IN_3") (pintype "input"))
      (node (ref "R29") (pin "2") (pinfunction "2_2") (pintype "passive"))
      (node (ref "TM8") (pin "2") (pinfunction "S_2") (pintype "passive"))
      (node (ref "U12") (pin "11") (pinfunction "WB_11") (pintype "bidirectional"))
    )
    (net (code "11") (name "ECHO") (class "Default")
      (node (ref "J1") (pin "3") (pinfunction "3_3") (pintype "passive"))
      (node (ref "MSP1") (pin "21") (pinfunction "P5.2/TA1.0/TA1CLK/ACLK/S36_21") (pintype "bidirectional"))
    )
    (net (code "12") (name "ECHO_GATE") (class "Default")
      (node (ref "JP42") (pin "2") (pinfunction "2_2") (pintype "passive"))
      (node (ref "U6") (pin "6") (pinfunction "ON_6") (pintype "bidirectional"))
    )
    (net (code "13") (name "ECHO_POT_1") (class "Default")
      (node (ref "JP18") (pin "1") (pinfunction "1_1") (pintype "passive"))
      (node (ref "R22") (pin "2") (pinfunction "2_2") (pintype "passive"))
      (node (ref "TM3") (pin "2") (pinfunction "S_2") (pintype "passive"))
      (node (ref "U5") (pin "14") (pinfunction "WA_14") (pintype "passive"))
      (node (ref "U7") (pin "3") (pinfunction "IN1+_3") (pintype "input"))
    )
    (net (code "14") (name "ECHO_POT_2") (class "Default")
      (node (ref "JP19") (pin "1") (pinfunction "1_1") (pintype "passive"))
      (node (ref "R21") (pin "1") (pinfunction "1_1") (pintype "passive"))
      (node (ref "TM4") (pin "2") (pinfunction "S_2") (pintype "passive"))
      (node (ref "U5") (pin "11") (pinfunction "WB_11") (pintype "bidirectional"))
      (node (ref "U7") (pin "5") (pinfunction "IN1+_5") (pintype "input"))
    )
    (net (code "15") (name "ECHO_UFOP_GATE") (class "Default")
      (node (ref "JP21") (pin "1") (pinfunction "1_1") (pintype "passive"))
      (node (ref "JP42") (pin "1") (pinfunction "1_1") (pintype "passive"))
      (node (ref "MSP1") (pin "18") (pinfunction "P10.2/TA1.0/SMCLK/S39_18") (pintype "bidirectional"))
    )
    (net (code "16") (name "ECHO_UFOP_INT") (class "Default")
      (node (ref "JP20") (pin "1") (pinfunction "1_1") (pintype "passive"))
      (node (ref "MSP1") (pin "19") (pinfunction "P5.0/TA1.1/MCLK/S38_19") (pintype "bidirectional"))
      (node (ref "U7") (pin "7") (pinfunction "OUT1_7") (pintype "output"))
      (node (ref "ZENER1") (pin "CATHODE") (pinfunction "C_CATHODE") (pintype "passive"))
    )
    (net (code "17") (name "ECHO_UFOP_PWR") (class "Default")
      (node (ref "JP40") (pin "2") (pinfunction "2_2") (pintype "passive"))
      (node (ref "R22") (pin "1") (pinfunction "1_1") (pintype "passive"))
      (node (ref "U5") (pin "1") (pinfunction "VDD_1") (pintype "bidirectional"))
      (node (ref "U7") (pin "8") (pinfunction "VCC+_8") (pintype "bidirectional"))
    )
    (net (code "18") (name "ECHO_UFOP_VCC") (class "Default")
      (node (ref "J1") (pin "5") (pinfunction "5_5") (pintype "passive"))
      (node (ref "U6") (pin "1") (pinfunction "VOUT_1") (pintype "bidirectional"))
    )
    (net (code "19") (name "GDO0") (class "Default")
      (node (ref "J3") (pin "1") (pinfunction "1_1") (pintype "passive"))
      (node (ref "MSP1") (pin "7") (pinfunction "P6.0/R23_7") (pintype "bidirectional"))
    )
    (net (code "20") (name "GDO2") (class "Default")
      (node (ref "J4") (pin "1") (pinfunction "1_1") (pintype "passive"))
      (node (ref "MSP1") (pin "3") (pinfunction "P1.5/UCB0STE/UCA0CLK/TA0.0/S0_3") (pintype "bidirectional"))
    )
    (net (code "21") (name "GND") (class "Default")
      (node (ref "BATT") (pin "1") (pinfunction "1_1") (pintype "passive"))
      (node (ref "C10") (pin "1") (pinfunction "1_1") (pintype "passive"))
      (node (ref "C11") (pin "2") (pinfunction "2_2") (pintype "passive"))
      (node (ref "C12") (pin "2") (pinfunction "2_2") (pintype "passive"))
      (node (ref "C13") (pin "2") (pinfunction "2_2") (pintype "passive"))
      (node (ref "C14") (pin "1") (pinfunction "1_1") (pintype "passive"))
      (node (ref "C15") (pin "1") (pinfunction "1_1") (pintype "passive"))
      (node (ref "C3") (pin "1") (pinfunction "1_1") (pintype "passive"))
      (node (ref "C4") (pin "1") (pinfunction "1_1") (pintype "passive"))
      (node (ref "C5") (pin "2") (pinfunction "2_2") (pintype "passive"))
      (node (ref "C6") (pin "2") (pinfunction "2_2") (pintype "passive"))
      (node (ref "C7") (pin "2") (pinfunction "2_2") (pintype "passive"))
      (node (ref "C8") (pin "2") (pinfunction "2_2") (pintype "passive"))
      (node (ref "C9") (pin "2") (pinfunction "2_2") (pintype "passive"))
      (node (ref "HI-LO-1") (pin "2") (pinfunction "GND_2") (pintype "power_in"))
      (node (ref "HI-LO-2") (pin "2") (pinfunction "GND_2") (pintype "power_in"))
      (node (ref "J1") (pin "1") (pinfunction "1_1") (pintype "passive"))
      (node (ref "J1") (pin "2") (pinfunction "2_2") (pintype "passive"))
      (node (ref "J2") (pin "3") (pinfunction "VSS(GND)_3") (pintype "power_in"))
      (node (ref "J2") (pin "5") (pinfunction "ICSP_CLK/PGC_5") (pintype "output"))
      (node (ref "J3") (pin "4") (pinfunction "4_4") (pintype "passive"))
      (node (ref "LO-HI-1") (pin "2") (pinfunction "GND_2") (pintype "power_in"))
      (node (ref "LO-HI-2") (pin "2") (pinfunction "GND_2") (pintype "power_in"))
      (node (ref "MIC") (pin "2") (pinfunction "GND_2") (pintype "bidirectional"))
      (node (ref "MSP1") (pin "26") (pinfunction "DVSS1_26") (pintype "bidirectional"))
      (node (ref "MSP1") (pin "57") (pinfunction "DVSS2_57") (pintype "bidirectional"))
      (node (ref "MSP1") (pin "80") (pinfunction "AVSS3_80") (pintype "bidirectional"))
      (node (ref "MSP1") (pin "83") (pinfunction "AVSS1_83") (pintype "bidirectional"))
      (node (ref "MSP1") (pin "86") (pinfunction "AVSS2_86") (pintype "bidirectional"))
      (node (ref "MSP1") (pin "98") (pinfunction "DVSS3_98") (pintype "bidirectional"))
      (node (ref "NCP") (pin "2") (pinfunction "GND_2") (pintype "bidirectional"))
      (node (ref "R1") (pin "2") (pinfunction "2_2") (pintype "passive"))
      (node (ref "R10") (pin "2") (pinfunction "2_2") (pintype "passive"))
      (node (ref "R12") (pin "2") (pinfunction "2_2") (pintype "passive"))
      (node (ref "R15") (pin "1") (pinfunction "1_1") (pintype "passive"))
      (node (ref "R18") (pin "1") (pinfunction "1_1") (pintype "passive"))
      (node (ref "R20") (pin "1") (pinfunction "1_1") (pintype "passive"))
      (node (ref "R25") (pin "2") (pinfunction "2_2") (pintype "passive"))
      (node (ref "R28") (pin "2") (pinfunction "2_2") (pintype "passive"))
      (node (ref "R33") (pin "2") (pinfunction "2_2") (pintype "passive"))
      (node (ref "R6") (pin "1") (pinfunction "1_1") (pintype "passive"))
      (node (ref "SOLAR1") (pin "1") (pinfunction "1_1") (pintype "passive"))
      (node (ref "SOLAR2") (pin "1") (pinfunction "1_1") (pintype "passive"))
      (node (ref "TM1") (pin "1") (pinfunction "A_1") (pintype "passive"))
      (node (ref "TM2") (pin "1") (pinfunction "A_1") (pintype "passive"))
      (node (ref "TM3") (pin "1") (pinfunction "A_1") (pintype "passive"))
      (node (ref "TM4") (pin "1") (pinfunction "A_1") (pintype "passive"))
      (node (ref "TM5") (pin "1") (pinfunction "A_1") (pintype "passive"))
      (node (ref "TM6") (pin "1") (pinfunction "A_1") (pintype "passive"))
      (node (ref "TM7") (pin "1") (pinfunction "A_1") (pintype "passive"))
      (node (ref "TM8") (pin "1") (pinfunction "A_1") (pintype "passive"))
      (node (ref "U10") (pin "4") (pinfunction "VCC-_4") (pintype "bidirectional"))
      (node (ref "U11") (pin "10") (pinfunction "LB_10") (pintype "bidirectional"))
      (node (ref "U11") (pin "13") (pinfunction "LA_13") (pintype "passive"))
      (node (ref "U11") (pin "4") (pinfunction "A0_4") (pintype "bidirectional"))
      (node (ref "U11") (pin "5") (pinfunction "A1_5") (pintype "bidirectional"))
      (node (ref "U11") (pin "6") (pinfunction "A2_6") (pintype "bidirectional"))
      (node (ref "U11") (pin "7") (pinfunction "GND_7") (pintype "bidirectional"))
      (node (ref "U11") (pin "TH") (pinfunction "GND_TH") (pintype "bidirectional"))
      (node (ref "U12") (pin "10") (pinfunction "LB_10") (pintype "bidirectional"))
      (node (ref "U12") (pin "13") (pinfunction "LA_13") (pintype "passive"))
      (node (ref "U12") (pin "4") (pinfunction "A0_4") (pintype "bidirectional"))
      (node (ref "U12") (pin "5") (pinfunction "A1_5") (pintype "bidirectional"))
      (node (ref "U12") (pin "6") (pinfunction "A2_6") (pintype "bidirectional"))
      (node (ref "U12") (pin "7") (pinfunction "GND_7") (pintype "bidirectional"))
      (node (ref "U12") (pin "TH") (pinfunction "GND_TH") (pintype "bidirectional"))
      (node (ref "U3") (pin "10") (pinfunction "EXTI_10") (pintype "bidirectional"))
      (node (ref "U3") (pin "2") (pinfunction "WDI_2") (pintype "bidirectional"))
      (node (ref "U3") (pin "9") (pinfunction "VSS_9") (pintype "bidirectional"))
      (node (ref "U3") (pin "TH") (pinfunction "VSS_TH") (pintype "bidirectional"))
      (node (ref "U4") (pin "3") (pinfunction "GND_3") (pintype "bidirectional"))
      (node (ref "U5") (pin "10") (pinfunction "LB_10") (pintype "bidirectional"))
      (node (ref "U5") (pin "13") (pinfunction "LA_13") (pintype "passive"))
      (node (ref "U5") (pin "4") (pinfunction "A0_4") (pintype "bidirectional"))
      (node (ref "U5") (pin "5") (pinfunction "A1_5") (pintype "bidirectional"))
      (node (ref "U5") (pin "6") (pinfunction "A2_6") (pintype "bidirectional"))
      (node (ref "U5") (pin "7") (pinfunction "GND_7") (pintype "bidirectional"))
      (node (ref "U5") (pin "TH") (pinfunction "GND_TH") (pintype "bidirectional"))
      (node (ref "U6") (pin "2") (pinfunction "GND_2") (pintype "bidirectional"))
      (node (ref "U7") (pin "4") (pinfunction "VCC-_4") (pintype "bidirectional"))
      (node (ref "U8") (pin "10") (pinfunction "LB_10") (pintype "bidirectional"))
      (node (ref "U8") (pin "13") (pinfunction "LA_13") (pintype "passive"))
      (node (ref "U8") (pin "4") (pinfunction "A0_4") (pintype "bidirectional"))
      (node (ref "U8") (pin "5") (pinfunction "A1_5") (pintype "bidirectional"))
      (node (ref "U8") (pin "6") (pinfunction "A2_6") (pintype "bidirectional"))
      (node (ref "U8") (pin "7") (pinfunction "GND_7") (pintype "bidirectional"))
      (node (ref "U8") (pin "TH") (pinfunction "GND_TH") (pintype "bidirectional"))
      (node (ref "U9") (pin "2") (pinfunction "GND_2") (pintype "bidirectional"))
      (node (ref "ZENER") (pin "ANODE") (pinfunction "A_ANODE") (pintype "passive"))
      (node (ref "ZENER1") (pin "ANODE") (pinfunction "A_ANODE") (pintype "passive"))
      (node (ref "ZENER2") (pin "ANODE") (pinfunction "A_ANODE") (pintype "passive"))
    )
    (net (code "22") (name "HARVESTER_IN") (class "Default")
      (node (ref "D1") (pin "C") (pinfunction "C_C") (pintype "passive"))
      (node (ref "D2") (pin "C") (pinfunction "C_C") (pintype "passive"))
      (node (ref "JP14") (pin "1") (pinfunction "1_1") (pintype "passive"))
      (node (ref "S1") (pin "1") (pinfunction "O_1") (pintype "passive"))
    )
    (net (code "23") (name "HI-LO-DIFF-1") (class "Default")
      (node (ref "HI-LO-2") (pin "4") (pinfunction "OUT_4") (pintype "output"))
      (node (ref "JP8") (pin "1") (pinfunction "1_1") (pintype "passive"))
      (node (ref "MSP1") (pin "51") (pinfunction "P2.0/UCA0SIMO/UCA0TXD/TB0.6/TB0CLK_51") (pintype "bidirectional"))
      (node (ref "R30") (pin "2") (pinfunction "2_2") (pintype "passive"))
    )
    (net (code "24") (name "HI-LO-DIFF-2") (class "Default")
      (node (ref "HI-LO-1") (pin "4") (pinfunction "OUT_4") (pintype "output"))
      (node (ref "JP29") (pin "1") (pinfunction "1_1") (pintype "passive"))
      (node (ref "MSP1") (pin "49") (pinfunction "P2.2/UCA0CLK/TB0.4/RTCCLK_49") (pintype "bidirectional"))
      (node (ref "R4") (pin "1") (pinfunction "1_1") (pintype "passive"))
    )
    (net (code "25") (name "LED_1") (class "Default")
      (node (ref "LED1") (pin "A") (pinfunction "A_A") (pintype "passive"))
      (node (ref "MSP1") (pin "13") (pinfunction "P6.6/TB0.2/COM3_13") (pintype "bidirectional"))
    )
    (net (code "26") (name "LED_2") (class "Default")
      (node (ref "LED2") (pin "A") (pinfunction "A_A") (pintype "passive"))
      (node (ref "MSP1") (pin "12") (pinfunction "P6.5/TB0.1/COM2_12") (pintype "bidirectional"))
    )
    (net (code "27") (name "LO-HI-DIFF-1") (class "Default")
      (node (ref "JP9") (pin "1") (pinfunction "1_1") (pintype "passive"))
      (node (ref "LO-HI-2") (pin "4") (pinfunction "OUT_4") (pintype "output"))
      (node (ref "MSP1") (pin "50") (pinfunction "P2.1/UCA0SOMI/UCA0RXD/TB0.5/DMAE0_50") (pintype "bidirectional"))
      (node (ref "R34") (pin "1") (pinfunction "1_1") (pintype "passive"))
    )
    (net (code "28") (name "LO-HI-DIFF-2") (class "Default")
      (node (ref "JP30") (pin "1") (pinfunction "1_1") (pintype "passive"))
      (node (ref "LO-HI-1") (pin "4") (pinfunction "OUT_4") (pintype "output"))
      (node (ref "MSP1") (pin "48") (pinfunction "P2.3/UCA0STE/TB0OUTH_48") (pintype "bidirectional"))
      (node (ref "R26") (pin "1") (pinfunction "1_1") (pintype "passive"))
    )
    (net (code "29") (name "MISO") (class "Default")
      (node (ref "J4") (pin "2") (pinfunction "2_2") (pintype "passive"))
      (node (ref "MSP1") (pin "5") (pinfunction "P1.7/UCB0SOMI/UCB0SCL/TA0.2_5") (pintype "bidirectional"))
    )
    (net (code "30") (name "MOSI") (class "Default")
      (node (ref "J4") (pin "4") (pinfunction "4_4") (pintype "passive"))
      (node (ref "MSP1") (pin "4") (pinfunction "P1.6/UCB0SIMO/UCB0SDA/TA0.1_4") (pintype "bidirectional"))
    )
    (net (code "31") (name "Net-(LED1-PadC)") (class "Default")
      (node (ref "LED1") (pin "C") (pinfunction "C_C") (pintype "passive"))
      (node (ref "R12") (pin "1") (pinfunction "1_1") (pintype "passive"))
    )
    (net (code "32") (name "Net-(LED2-PadC)") (class "Default")
      (node (ref "LED2") (pin "C") (pinfunction "C_C") (pintype "passive"))
      (node (ref "R25") (pin "1") (pinfunction "1_1") (pintype "passive"))
    )
    (net (code "33") (name "Net-(MIC-HTH)") (class "Default")
      (node (ref "MIC") (pin "1") (pinfunction "HTH_1") (pintype "bidirectional"))
      (node (ref "R14") (pin "1") (pinfunction "1_1") (pintype "passive"))
      (node (ref "R15") (pin "2") (pinfunction "2_2") (pintype "passive"))
    )
    (net (code "34") (name "Net-(MIC-LTH)") (class "Default")
      (node (ref "MIC") (pin "3") (pinfunction "LTH_3") (pintype "bidirectional"))
      (node (ref "R13") (pin "1") (pinfunction "1_1") (pintype "passive"))
      (node (ref "R14") (pin "2") (pinfunction "2_2") (pintype "passive"))
    )
    (net (code "35") (name "Net-(MSP1-P3.6{slash}UCA1CLK{slash}TB0.2{slash}S23)") (class "Default")
      (node (ref "JP49") (pin "1") (pinfunction "1_1") (pintype "passive"))
      (node (ref "MSP1") (pin "42") (pinfunction "P3.6/UCA1CLK/TB0.2/S23_42") (pintype "bidirectional"))
    )
    (net (code "36") (name "Net-(MSP1-P3.7{slash}UCA1STE{slash}TB0.3{slash}S22)") (class "Default")
      (node (ref "JP48") (pin "1") (pinfunction "1_1") (pintype "passive"))
      (node (ref "MSP1") (pin "43") (pinfunction "P3.7/UCA1STE/TB0.3/S22_43") (pintype "bidirectional"))
    )
    (net (code "37") (name "Net-(MSP1-P4.2{slash}UCA0SIMO{slash}UCA0TXD{slash}UCB1CLK)") (class "Default")
      (node (ref "JP47") (pin "1") (pinfunction "1_1") (pintype "passive"))
      (node (ref "MSP1") (pin "100") (pinfunction "P4.2/UCA0SIMO/UCA0TXD/UCB1CLK_100") (pintype "bidirectional"))
    )
    (net (code "38") (name "Net-(MSP1-P4.3{slash}UCA0SOMI{slash}UCA0RXD{slash}UCB1STE)") (class "Default")
      (node (ref "JP46") (pin "1") (pinfunction "1_1") (pintype "passive"))
      (node (ref "MSP1") (pin "1") (pinfunction "P4.3/UCA0SOMI/UCA0RXD/UCB1STE_1") (pintype "bidirectional"))
    )
    (net (code "39") (name "Net-(MSP1-P8.0{slash}RTCCLK{slash}S21)") (class "Default")
      (node (ref "JP44") (pin "1") (pinfunction "1_1") (pintype "passive"))
      (node (ref "MSP1") (pin "44") (pinfunction "P8.0/RTCCLK/S21_44") (pintype "bidirectional"))
    )
    (net (code "40") (name "Net-(MSP1-P8.1{slash}DMAE0{slash}S20)") (class "Default")
      (node (ref "JP45") (pin "1") (pinfunction "1_1") (pintype "passive"))
      (node (ref "MSP1") (pin "45") (pinfunction "P8.1/DMAE0/S20_45") (pintype "bidirectional"))
    )
    (net (code "41") (name "Net-(R10-Pad1)") (class "Default")
      (node (ref "R10") (pin "1") (pinfunction "1_1") (pintype "passive"))
      (node (ref "R2") (pin "2") (pinfunction "2_2") (pintype "passive"))
      (node (ref "R9") (pin "2") (pinfunction "2_2") (pintype "passive"))
    )
    (net (code "42") (name "Net-(R27-Pad2)") (class "Default")
      (node (ref "R27") (pin "2") (pinfunction "2_2") (pintype "passive"))
      (node (ref "R32") (pin "2") (pinfunction "2_2") (pintype "passive"))
      (node (ref "R33") (pin "1") (pinfunction "1_1") (pintype "passive"))
    )
    (net (code "43") (name "Net-(U3-VBAT)") (class "Default")
      (node (ref "C10") (pin "2") (pinfunction "2_2") (pintype "passive"))
      (node (ref "U3") (pin "5") (pinfunction "VBAT_5") (pintype "bidirectional"))
    )
    (net (code "44") (name "Net-(U4-VOUT)") (class "Default")
      (node (ref "R19") (pin "2") (pinfunction "2_2") (pintype "passive"))
      (node (ref "U4") (pin "2") (pinfunction "VOUT_2") (pintype "bidirectional"))
    )
    (net (code "45") (name "Net-(U6-VBIAS)") (class "Default")
      (node (ref "C12") (pin "1") (pinfunction "1_1") (pintype "passive"))
      (node (ref "D4") (pin "C") (pinfunction "C_C") (pintype "passive"))
      (node (ref "R21") (pin "2") (pinfunction "2_2") (pintype "passive"))
      (node (ref "U6") (pin "4") (pinfunction "VIN_4") (pintype "bidirectional"))
      (node (ref "U6") (pin "5") (pinfunction "VBIAS_5") (pintype "bidirectional"))
    )
    (net (code "46") (name "Net-(U7A-OUT1)") (class "Default")
      (node (ref "D4") (pin "A") (pinfunction "A_A") (pintype "passive"))
      (node (ref "U7") (pin "1") (pinfunction "OUT1_1") (pintype "output"))
    )
    (net (code "47") (name "Net-(U9-VBIAS)") (class "Default")
      (node (ref "C13") (pin "1") (pinfunction "1_1") (pintype "passive"))
      (node (ref "D5") (pin "C") (pinfunction "C_C") (pintype "passive"))
      (node (ref "R23") (pin "2") (pinfunction "2_2") (pintype "passive"))
      (node (ref "U9") (pin "4") (pinfunction "VIN_4") (pintype "bidirectional"))
      (node (ref "U9") (pin "5") (pinfunction "VBIAS_5") (pintype "bidirectional"))
    )
    (net (code "48") (name "Net-(U10A-OUT1)") (class "Default")
      (node (ref "D5") (pin "A") (pinfunction "A_A") (pintype "passive"))
      (node (ref "U10") (pin "1") (pinfunction "OUT1_1") (pintype "output"))
    )
    (net (code "49") (name "POWER_IN") (class "Default")
      (node (ref "C4") (pin "2") (pinfunction "2_2") (pintype "passive"))
      (node (ref "JP11") (pin "1") (pinfunction "1_1") (pintype "passive"))
      (node (ref "MIC") (pin "5") (pinfunction "VDD_5") (pintype "bidirectional"))
      (node (ref "R13") (pin "2") (pinfunction "2_2") (pintype "passive"))
      (node (ref "S1") (pin "2") (pinfunction "P_2") (pintype "passive"))
      (node (ref "ZENER2") (pin "CATHODE") (pinfunction "C_CATHODE") (pintype "passive"))
    )
    (net (code "50") (name "RADIO_GATE") (class "Default")
      (node (ref "JP39") (pin "2") (pinfunction "2_2") (pintype "passive"))
      (node (ref "U9") (pin "6") (pinfunction "ON_6") (pintype "bidirectional"))
    )
    (net (code "51") (name "RADIO_POT_1") (class "Default")
      (node (ref "JP2") (pin "1") (pinfunction "1_1") (pintype "passive"))
      (node (ref "R24") (pin "2") (pinfunction "2_2") (pintype "passive"))
      (node (ref "TM1") (pin "2") (pinfunction "S_2") (pintype "passive"))
      (node (ref "U10") (pin "3") (pinfunction "IN1+_3") (pintype "input"))
      (node (ref "U8") (pin "14") (pinfunction "WA_14") (pintype "passive"))
    )
    (net (code "52") (name "RADIO_POT_2") (class "Default")
      (node (ref "JP15") (pin "1") (pinfunction "1_1") (pintype "passive"))
      (node (ref "R23") (pin "1") (pinfunction "1_1") (pintype "passive"))
      (node (ref "TM2") (pin "2") (pinfunction "S_2") (pintype "passive"))
      (node (ref "U10") (pin "5") (pinfunction "IN1+_5") (pintype "input"))
      (node (ref "U8") (pin "11") (pinfunction "WB_11") (pintype "bidirectional"))
    )
    (net (code "53") (name "RADIO_UFOP_GATE") (class "Default")
      (node (ref "JP17") (pin "1") (pinfunction "1_1") (pintype "passive"))
      (node (ref "JP39") (pin "1") (pinfunction "1_1") (pintype "passive"))
      (node (ref "MSP1") (pin "9") (pinfunction "P6.2/COUT/R03_9") (pintype "bidirectional"))
    )
    (net (code "54") (name "RADIO_UFOP_INT") (class "Default")
      (node (ref "JP16") (pin "1") (pinfunction "1_1") (pintype "passive"))
      (node (ref "MSP1") (pin "10") (pinfunction "P6.3/COM0_10") (pintype "bidirectional"))
      (node (ref "U10") (pin "7") (pinfunction "OUT1_7") (pintype "output"))
      (node (ref "ZENER") (pin "CATHODE") (pinfunction "C_CATHODE") (pintype "passive"))
    )
    (net (code "55") (name "RADIO_UFOP_PWR") (class "Default")
      (node (ref "JP38") (pin "2") (pinfunction "2_2") (pintype "passive"))
      (node (ref "R24") (pin "1") (pinfunction "1_1") (pintype "passive"))
      (node (ref "U10") (pin "8") (pinfunction "VCC+_8") (pintype "bidirectional"))
      (node (ref "U8") (pin "1") (pinfunction "VDD_1") (pintype "bidirectional"))
    )
    (net (code "56") (name "RADIO_UFOP_VCC") (class "Default")
      (node (ref "J3") (pin "3") (pinfunction "3_3") (pintype "passive"))
      (node (ref "U9") (pin "1") (pinfunction "VOUT_1") (pintype "bidirectional"))
    )
    (net (code "57") (name "REF") (class "Default")
      (node (ref "JP32") (pin "1") (pinfunction "1_1") (pintype "passive"))
      (node (ref "R19") (pin "1") (pinfunction "1_1") (pintype "passive"))
      (node (ref "R20") (pin "2") (pinfunction "2_2") (pintype "passive"))
      (node (ref "U10") (pin "2") (pinfunction "IN1-_2") (pintype "input"))
      (node (ref "U10") (pin "6") (pinfunction "IN1-_6") (pintype "input"))
      (node (ref "U7") (pin "2") (pinfunction "IN1-_2") (pintype "input"))
      (node (ref "U7") (pin "6") (pinfunction "IN1-_6") (pintype "input"))
    )
    (net (code "58") (name "REFPWR") (class "Default")
      (node (ref "JP41") (pin "2") (pinfunction "2_2") (pintype "passive"))
      (node (ref "U4") (pin "1") (pinfunction "VIN_1") (pintype "bidirectional"))
    )
    (net (code "59") (name "RST") (class "Default")
      (node (ref "C11") (pin "1") (pinfunction "1_1") (pintype "passive"))
      (node (ref "C3") (pin "2") (pinfunction "2_2") (pintype "passive"))
      (node (ref "J2") (pin "1") (pinfunction "VPP/MCLR_1") (pintype "passive"))
      (node (ref "JP25") (pin "1") (pinfunction "1_1") (pintype "passive"))
      (node (ref "MSP1") (pin "29") (pinfunction "RST/NMI/SBWTDIO_29") (pintype "bidirectional"))
      (node (ref "R11") (pin "1") (pinfunction "1_1") (pintype "passive"))
    )
    (net (code "60") (name "SCLK") (class "Default")
      (node (ref "J4") (pin "3") (pinfunction "3_3") (pintype "passive"))
      (node (ref "MSP1") (pin "2") (pinfunction "P1.4/UCB0CLK/UCA0STE/TA1.0/S1_2") (pintype "bidirectional"))
    )
    (net (code "61") (name "SCL_CTRL") (class "Default")
      (node (ref "JP23") (pin "1") (pinfunction "1_1") (pintype "passive"))
      (node (ref "MSP1") (pin "25") (pinfunction "P3.2/UCB1SOMI/UCB1SCL/S32_25") (pintype "bidirectional"))
      (node (ref "R16") (pin "1") (pinfunction "1_1") (pintype "passive"))
      (node (ref "U11") (pin "2") (pinfunction "SCL_2") (pintype "bidirectional"))
      (node (ref "U12") (pin "2") (pinfunction "SCL_2") (pintype "bidirectional"))
      (node (ref "U3") (pin "7") (pinfunction "SCL_7") (pintype "bidirectional"))
      (node (ref "U5") (pin "2") (pinfunction "SCL_2") (pintype "bidirectional"))
      (node (ref "U8") (pin "2") (pinfunction "SCL_2") (pintype "bidirectional"))
    )
    (net (code "62") (name "SDA_CTRL") (class "Default")
      (node (ref "JP22") (pin "1") (pinfunction "1_1") (pintype "passive"))
      (node (ref "MSP1") (pin "24") (pinfunction "P3.1/UCB1SIMO/UCB1SDA/S33_24") (pintype "bidirectional"))
      (node (ref "R17") (pin "1") (pinfunction "1_1") (pintype "passive"))
      (node (ref "U11") (pin "3") (pinfunction "SDA_3") (pintype "bidirectional"))
      (node (ref "U12") (pin "3") (pinfunction "SDA_3") (pintype "bidirectional"))
      (node (ref "U3") (pin "6") (pinfunction "SDA_6") (pintype "bidirectional"))
      (node (ref "U5") (pin "3") (pinfunction "SDA_3") (pintype "bidirectional"))
      (node (ref "U8") (pin "3") (pinfunction "SDA_3") (pintype "bidirectional"))
    )
    (net (code "63") (name "SOLAR1") (class "Default")
      (node (ref "D1") (pin "A") (pinfunction "A_A") (pintype "passive"))
      (node (ref "JP34") (pin "2") (pinfunction "2_2") (pintype "passive"))
      (node (ref "JP36") (pin "2") (pinfunction "2_2") (pintype "passive"))
      (node (ref "R7") (pin "1") (pinfunction "1_1") (pintype "passive"))
      (node (ref "SOL1") (pin "1") (pinfunction "1_1") (pintype "passive"))
      (node (ref "SOLAR1") (pin "2") (pinfunction "2_2") (pintype "passive"))
    )
    (net (code "64") (name "SOLAR1-1") (class "Default")
      (node (ref "C16") (pin "1") (pinfunction "1_1") (pintype "passive"))
      (node (ref "JP34") (pin "1") (pinfunction "1_1") (pintype "passive"))
    )
    (net (code "65") (name "SOLAR1-2") (class "Default")
      (node (ref "C17") (pin "1") (pinfunction "1_1") (pintype "passive"))
      (node (ref "JP36") (pin "1") (pinfunction "1_1") (pintype "passive"))
    )
    (net (code "66") (name "SOLAR1IN") (class "Default")
      (node (ref "C15") (pin "2") (pinfunction "2_2") (pintype "passive"))
      (node (ref "JP26") (pin "1") (pinfunction "1_1") (pintype "passive"))
      (node (ref "JP3") (pin "1") (pinfunction "1_1") (pintype "passive"))
      (node (ref "R18") (pin "2") (pinfunction "2_2") (pintype "passive"))
      (node (ref "R7") (pin "2") (pinfunction "2_2") (pintype "passive"))
    )
    (net (code "67") (name "SOLAR1MC") (class "Default")
      (node (ref "JP3") (pin "2") (pinfunction "2_2") (pintype "passive"))
      (node (ref "MSP1") (pin "65") (pinfunction "P1.1/TA0.2/TA1CLK/COUT/A1/C1/VREF+/VEREF+_65") (pintype "bidirectional"))
    )
    (net (code "68") (name "SOLAR2") (class "Default")
      (node (ref "D2") (pin "A") (pinfunction "A_A") (pintype "passive"))
      (node (ref "JP4") (pin "2") (pinfunction "2_2") (pintype "passive"))
      (node (ref "JP5") (pin "2") (pinfunction "2_2") (pintype "passive"))
      (node (ref "JP6") (pin "1") (pinfunction "1_1") (pintype "passive"))
      (node (ref "R5") (pin "1") (pinfunction "1_1") (pintype "passive"))
      (node (ref "SOLAR2") (pin "2") (pinfunction "2_2") (pintype "passive"))
    )
    (net (code "69") (name "SOLAR2-1") (class "Default")
      (node (ref "C2") (pin "1") (pinfunction "1_1") (pintype "passive"))
      (node (ref "JP4") (pin "1") (pinfunction "1_1") (pintype "passive"))
    )
    (net (code "70") (name "SOLAR2-2") (class "Default")
      (node (ref "C1") (pin "1") (pinfunction "1_1") (pintype "passive"))
      (node (ref "JP5") (pin "1") (pinfunction "1_1") (pintype "passive"))
    )
    (net (code "71") (name "SOLAR2IN") (class "Default")
      (node (ref "C14") (pin "2") (pinfunction "2_2") (pintype "passive"))
      (node (ref "JP27") (pin "1") (pinfunction "1_1") (pintype "passive"))
      (node (ref "JP43") (pin "1") (pinfunction "1_1") (pintype "passive"))
      (node (ref "R5") (pin "2") (pinfunction "2_2") (pintype "passive"))
      (node (ref "R6") (pin "2") (pinfunction "2_2") (pintype "passive"))
    )
    (net (code "72") (name "SOLAR2MC") (class "Default")
      (node (ref "JP43") (pin "2") (pinfunction "2_2") (pintype "passive"))
      (node (ref "MSP1") (pin "66") (pinfunction "P1.0/TA0.1/DMAE0/RTCCLK/A0/C0/VREF-/VEREF-_66") (pintype "bidirectional"))
    )
    (net (code "73") (name "TEST") (class "Default")
      (node (ref "J2") (pin "6") (pinfunction "LVP_6") (pintype "bidirectional"))
      (node (ref "JP24") (pin "1") (pinfunction "1_1") (pintype "passive"))
      (node (ref "MSP1") (pin "28") (pinfunction "TEST/SBWTCK_28") (pintype "bidirectional"))
    )
    (net (code "74") (name "TLVPWR1") (class "Default")
      (node (ref "HI-LO-2") (pin "5") (pinfunction "V+_5") (pintype "power_in"))
      (node (ref "JP1") (pin "2") (pinfunction "2_2") (pintype "passive"))
      (node (ref "R8") (pin "1") (pinfunction "1_1") (pintype "passive"))
      (node (ref "R9") (pin "1") (pinfunction "1_1") (pintype "passive"))
    )
    (net (code "75") (name "TLVPWR2") (class "Default")
      (node (ref "JP33") (pin "2") (pinfunction "2_2") (pintype "passive"))
      (node (ref "LO-HI-2") (pin "5") (pinfunction "V+_5") (pintype "power_in"))
      (node (ref "R3") (pin "1") (pinfunction "1_1") (pintype "passive"))
    )
    (net (code "76") (name "TLVPWR3") (class "Default")
      (node (ref "HI-LO-1") (pin "5") (pinfunction "V+_5") (pintype "power_in"))
      (node (ref "JP35") (pin "2") (pinfunction "2_2") (pintype "passive"))
      (node (ref "R31") (pin "1") (pinfunction "1_1") (pintype "passive"))
      (node (ref "R32") (pin "1") (pinfunction "1_1") (pintype "passive"))
    )
    (net (code "77") (name "TLVPWR4") (class "Default")
      (node (ref "JP37") (pin "2") (pinfunction "2_2") (pintype "passive"))
      (node (ref "LO-HI-1") (pin "5") (pinfunction "V+_5") (pintype "power_in"))
      (node (ref "R29") (pin "1") (pinfunction "1_1") (pintype "passive"))
    )
    (net (code "78") (name "TRIG") (class "Default")
      (node (ref "J1") (pin "4") (pinfunction "4_4") (pintype "passive"))
      (node (ref "MSP1") (pin "22") (pinfunction "P5.3/UCB1STE/S35_22") (pintype "bidirectional"))
    )
    (net (code "79") (name "VCC") (class "Default")
      (node (ref "C5") (pin "1") (pinfunction "1_1") (pintype "passive"))
      (node (ref "C6") (pin "1") (pinfunction "1_1") (pintype "passive"))
      (node (ref "C7") (pin "1") (pinfunction "1_1") (pintype "passive"))
      (node (ref "C8") (pin "1") (pinfunction "1_1") (pintype "passive"))
      (node (ref "C9") (pin "1") (pinfunction "1_1") (pintype "passive"))
      (node (ref "J2") (pin "2") (pinfunction "VDD_2") (pintype "power_in"))
      (node (ref "JP1") (pin "1") (pinfunction "1_1") (pintype "passive"))
      (node (ref "JP13") (pin "1") (pinfunction "1_1") (pintype "passive"))
      (node (ref "JP33") (pin "1") (pinfunction "1_1") (pintype "passive"))
      (node (ref "JP35") (pin "1") (pinfunction "1_1") (pintype "passive"))
      (node (ref "JP37") (pin "1") (pinfunction "1_1") (pintype "passive"))
      (node (ref "MSP1") (pin "27") (pinfunction "DVCC1_27") (pintype "bidirectional"))
      (node (ref "MSP1") (pin "58") (pinfunction "DVCC2_58") (pintype "bidirectional"))
      (node (ref "MSP1") (pin "79") (pinfunction "AVCC1_79") (pintype "bidirectional"))
      (node (ref "MSP1") (pin "99") (pinfunction "DVCC3_99") (pintype "bidirectional"))
      (node (ref "NCP") (pin "3") (pinfunction "OUT_3") (pintype "bidirectional"))
      (node (ref "R11") (pin "2") (pinfunction "2_2") (pintype "passive"))
      (node (ref "R16") (pin "2") (pinfunction "2_2") (pintype "passive"))
      (node (ref "R17") (pin "2") (pinfunction "2_2") (pintype "passive"))
      (node (ref "U3") (pin "13") (pinfunction "VCC_13") (pintype "bidirectional"))
    )
    (net (code "80") (name "VIN") (class "Default")
      (node (ref "JP12") (pin "1") (pinfunction "1_1") (pintype "passive"))
      (node (ref "JP38") (pin "1") (pinfunction "1_1") (pintype "passive"))
      (node (ref "JP40") (pin "1") (pinfunction "1_1") (pintype "passive"))
      (node (ref "JP41") (pin "1") (pinfunction "1_1") (pintype "passive"))
      (node (ref "MIC") (pin "4") (pinfunction "OUT_4") (pintype "bidirectional"))
      (node (ref "NCP") (pin "1") (pinfunction "CE_1") (pintype "bidirectional"))
      (node (ref "NCP") (pin "4") (pinfunction "VIN_4") (pintype "bidirectional"))
      (node (ref "U11") (pin "1") (pinfunction "VDD_1") (pintype "bidirectional"))
      (node (ref "U12") (pin "1") (pinfunction "VDD_1") (pintype "bidirectional"))
    )
    (net (code "81") (name "WP_CTRL_DIFF_1") (class "Default")
      (node (ref "MSP1") (pin "60") (pinfunction "P8.5/A6/C6_60") (pintype "bidirectional"))
      (node (ref "U11") (pin "9") (pinfunction "WP_9") (pintype "bidirectional"))
    )
    (net (code "82") (name "WP_CTRL_DIFF_2") (class "Default")
      (node (ref "MSP1") (pin "61") (pinfunction "P8.6/A5/C5_61") (pintype "bidirectional"))
      (node (ref "U12") (pin "9") (pinfunction "WP_9") (pintype "bidirectional"))
    )
    (net (code "83") (name "WP_CTRL_ECHO") (class "Default")
      (node (ref "MSP1") (pin "14") (pinfunction "P2.4/TB0.3/COM4/S43_14") (pintype "bidirectional"))
      (node (ref "U5") (pin "9") (pinfunction "WP_9") (pintype "bidirectional"))
    )
    (net (code "84") (name "WP_CTRL_RADIO") (class "Default")
      (node (ref "MSP1") (pin "11") (pinfunction "P6.4/TB0.0/COM1_11") (pintype "bidirectional"))
      (node (ref "U8") (pin "9") (pinfunction "WP_9") (pintype "bidirectional"))
    )
    (net (code "85") (name "unconnected-(J2-ICSP_DAT{slash}PGD-Pad4)") (class "Default")
      (node (ref "J2") (pin "4") (pinfunction "ICSP_DAT/PGD_4") (pintype "bidirectional"))
    )
    (net (code "86") (name "unconnected-(JP1-Pad3)") (class "Default")
      (node (ref "JP1") (pin "3") (pinfunction "3_3") (pintype "passive"))
    )
    (net (code "87") (name "unconnected-(JP3-Pad3)") (class "Default")
      (node (ref "JP3") (pin "3") (pinfunction "3_3") (pintype "passive"))
    )
    (net (code "88") (name "unconnected-(JP4-Pad3)") (class "Default")
      (node (ref "JP4") (pin "3") (pinfunction "3_3") (pintype "passive"))
    )
    (net (code "89") (name "unconnected-(JP5-Pad3)") (class "Default")
      (node (ref "JP5") (pin "3") (pinfunction "3_3") (pintype "passive"))
    )
    (net (code "90") (name "unconnected-(JP33-Pad3)") (class "Default")
      (node (ref "JP33") (pin "3") (pinfunction "3_3") (pintype "passive"))
    )
    (net (code "91") (name "unconnected-(JP34-Pad3)") (class "Default")
      (node (ref "JP34") (pin "3") (pinfunction "3_3") (pintype "passive"))
    )
    (net (code "92") (name "unconnected-(JP35-Pad3)") (class "Default")
      (node (ref "JP35") (pin "3") (pinfunction "3_3") (pintype "passive"))
    )
    (net (code "93") (name "unconnected-(JP36-Pad3)") (class "Default")
      (node (ref "JP36") (pin "3") (pinfunction "3_3") (pintype "passive"))
    )
    (net (code "94") (name "unconnected-(JP37-Pad3)") (class "Default")
      (node (ref "JP37") (pin "3") (pinfunction "3_3") (pintype "passive"))
    )
    (net (code "95") (name "unconnected-(JP38-Pad3)") (class "Default")
      (node (ref "JP38") (pin "3") (pinfunction "3_3") (pintype "passive"))
    )
    (net (code "96") (name "unconnected-(JP39-Pad3)") (class "Default")
      (node (ref "JP39") (pin "3") (pinfunction "3_3") (pintype "passive"))
    )
    (net (code "97") (name "unconnected-(JP40-Pad3)") (class "Default")
      (node (ref "JP40") (pin "3") (pinfunction "3_3") (pintype "passive"))
    )
    (net (code "98") (name "unconnected-(JP41-Pad3)") (class "Default")
      (node (ref "JP41") (pin "3") (pinfunction "3_3") (pintype "passive"))
    )
    (net (code "99") (name "unconnected-(JP42-Pad3)") (class "Default")
      (node (ref "JP42") (pin "3") (pinfunction "3_3") (pintype "passive"))
    )
    (net (code "100") (name "unconnected-(JP43-Pad3)") (class "Default")
      (node (ref "JP43") (pin "3") (pinfunction "3_3") (pintype "passive"))
    )
    (net (code "101") (name "unconnected-(MSP1-ESICI-Pad77)") (class "Default")
      (node (ref "MSP1") (pin "77") (pinfunction "ESICI_77") (pintype "bidirectional"))
    )
    (net (code "102") (name "unconnected-(MSP1-ESICOM-Pad78)") (class "Default")
      (node (ref "MSP1") (pin "78") (pinfunction "ESICOM_78") (pintype "bidirectional"))
    )
    (net (code "103") (name "unconnected-(MSP1-ESIVCC-Pad75)") (class "Default")
      (node (ref "MSP1") (pin "75") (pinfunction "ESIVCC_75") (pintype "bidirectional"))
    )
    (net (code "104") (name "unconnected-(MSP1-ESIVSS-Pad76)") (class "Default")
      (node (ref "MSP1") (pin "76") (pinfunction "ESIVSS_76") (pintype "bidirectional"))
    )
    (net (code "105") (name "unconnected-(MSP1-P1.2{slash}TA1.1{slash}TA0CLK{slash}COUT{slash}A2{slash}C2-Pad64)") (class "Default")
      (node (ref "MSP1") (pin "64") (pinfunction "P1.2/TA1.1/TA0CLK/COUT/A2/C2_64") (pintype "bidirectional"))
    )
    (net (code "106") (name "unconnected-(MSP1-P1.3{slash}TA1.2{slash}ESITEST4{slash}A3{slash}C3-Pad63)") (class "Default")
      (node (ref "MSP1") (pin "63") (pinfunction "P1.3/TA1.2/ESITEST4/A3/C3_63") (pintype "bidirectional"))
    )
    (net (code "107") (name "unconnected-(MSP1-P2.5{slash}TB0.4{slash}COM5{slash}S42-Pad15)") (class "Default")
      (node (ref "MSP1") (pin "15") (pinfunction "P2.5/TB0.4/COM5/S42_15") (pintype "bidirectional"))
    )
    (net (code "108") (name "unconnected-(MSP1-P2.6{slash}TB0.5{slash}ESIC1OUT{slash}COM6{slash}S41-Pad16)") (class "Default")
      (node (ref "MSP1") (pin "16") (pinfunction "P2.6/TB0.5/ESIC1OUT/COM6/S41_16") (pintype "bidirectional"))
    )
    (net (code "109") (name "unconnected-(MSP1-P2.7{slash}TB0.6{slash}ESIC2OUT{slash}COM7{slash}S40-Pad17)") (class "Default")
      (node (ref "MSP1") (pin "17") (pinfunction "P2.7/TB0.6/ESIC2OUT/COM7/S40_17") (pintype "bidirectional"))
    )
    (net (code "110") (name "unconnected-(MSP1-P3.0{slash}UCB1CLK{slash}S34-Pad23)") (class "Default")
      (node (ref "MSP1") (pin "23") (pinfunction "P3.0/UCB1CLK/S34_23") (pintype "bidirectional"))
    )
    (net (code "111") (name "unconnected-(MSP1-P3.3{slash}TA1.1{slash}TB0CLK{slash}S26-Pad39)") (class "Default")
      (node (ref "MSP1") (pin "39") (pinfunction "P3.3/TA1.1/TB0CLK/S26_39") (pintype "bidirectional"))
    )
    (net (code "112") (name "unconnected-(MSP1-P3.4{slash}UCA1SIMO{slash}UCA1TXD{slash}TB0.0{slash}S25-Pad40)") (class "Default")
      (node (ref "MSP1") (pin "40") (pinfunction "P3.4/UCA1SIMO/UCA1TXD/TB0.0/S25_40") (pintype "bidirectional"))
    )
    (net (code "113") (name "unconnected-(MSP1-P3.5{slash}UCA1SOMI{slash}UCA1RXD{slash}TB0.1{slash}S24-Pad41)") (class "Default")
      (node (ref "MSP1") (pin "41") (pinfunction "P3.5/UCA1SOMI/UCA1RXD/TB0.1/S24_41") (pintype "bidirectional"))
    )
    (net (code "114") (name "unconnected-(MSP1-P4.0{slash}UCB1SIMO{slash}UCB1SDA{slash}MCLK{slash}S3-Pad96)") (class "Default")
      (node (ref "MSP1") (pin "96") (pinfunction "P4.0/UCB1SIMO/UCB1SDA/MCLK/S3_96") (pintype "bidirectional"))
    )
    (net (code "115") (name "unconnected-(MSP1-P4.1{slash}UCB1SOMI{slash}UCB1SCL{slash}ACLK{slash}S2-Pad97)") (class "Default")
      (node (ref "MSP1") (pin "97") (pinfunction "P4.1/UCB1SOMI/UCB1SCL/ACLK/S2_97") (pintype "bidirectional"))
    )
    (net (code "116") (name "unconnected-(MSP1-P4.4{slash}UCB1STE{slash}TA1CLK{slash}S8-Pad91)") (class "Default")
      (node (ref "MSP1") (pin "91") (pinfunction "P4.4/UCB1STE/TA1CLK/S8_91") (pintype "bidirectional"))
    )
    (net (code "117") (name "unconnected-(MSP1-P4.5{slash}UCB1CLK{slash}TA1.0{slash}S7-Pad92)") (class "Default")
      (node (ref "MSP1") (pin "92") (pinfunction "P4.5/UCB1CLK/TA1.0/S7_92") (pintype "bidirectional"))
    )
    (net (code "118") (name "unconnected-(MSP1-P4.6{slash}UCB1SIMO{slash}UCB1SDA{slash}TA1.1{slash}S6-Pad93)") (class "Default")
      (node (ref "MSP1") (pin "93") (pinfunction "P4.6/UCB1SIMO/UCB1SDA/TA1.1/S6_93") (pintype "bidirectional"))
    )
    (net (code "119") (name "unconnected-(MSP1-P4.7{slash}UCB1SOMI{slash}UCB1SCL{slash}TA1.2{slash}S5-Pad94)") (class "Default")
      (node (ref "MSP1") (pin "94") (pinfunction "P4.7/UCB1SOMI/UCB1SCL/TA1.2/S5_94") (pintype "bidirectional"))
    )
    (net (code "120") (name "unconnected-(MSP1-P5.1{slash}TA1.2{slash}S37-Pad20)") (class "Default")
      (node (ref "MSP1") (pin "20") (pinfunction "P5.1/TA1.2/S37_20") (pintype "bidirectional"))
    )
    (net (code "121") (name "unconnected-(MSP1-P5.4{slash}UCA1SIMO{slash}UCA1TXD{slash}S12-Pad87)") (class "Default")
      (node (ref "MSP1") (pin "87") (pinfunction "P5.4/UCA1SIMO/UCA1TXD/S12_87") (pintype "bidirectional"))
    )
    (net (code "122") (name "unconnected-(MSP1-P5.5{slash}UCA1SOMI{slash}UCA1RXD{slash}S11-Pad88)") (class "Default")
      (node (ref "MSP1") (pin "88") (pinfunction "P5.5/UCA1SOMI/UCA1RXD/S11_88") (pintype "bidirectional"))
    )
    (net (code "123") (name "unconnected-(MSP1-P5.6{slash}UCA1CLK{slash}S10-Pad89)") (class "Default")
      (node (ref "MSP1") (pin "89") (pinfunction "P5.6/UCA1CLK/S10_89") (pintype "bidirectional"))
    )
    (net (code "124") (name "unconnected-(MSP1-P5.7{slash}UCA1STE{slash}TB0CLK{slash}S9-Pad90)") (class "Default")
      (node (ref "MSP1") (pin "90") (pinfunction "P5.7/UCA1STE/TB0CLK/S9_90") (pintype "bidirectional"))
    )
    (net (code "125") (name "unconnected-(MSP1-P6.7{slash}TA0CLK{slash}S31-Pad34)") (class "Default")
      (node (ref "MSP1") (pin "34") (pinfunction "P6.7/TA0CLK/S31_34") (pintype "bidirectional"))
    )
    (net (code "126") (name "unconnected-(MSP1-P7.0{slash}TA0CLK{slash}S17-Pad52)") (class "Default")
      (node (ref "MSP1") (pin "52") (pinfunction "P7.0/TA0CLK/S17_52") (pintype "bidirectional"))
    )
    (net (code "127") (name "unconnected-(MSP1-P7.1{slash}TA0.0{slash}S16-Pad53)") (class "Default")
      (node (ref "MSP1") (pin "53") (pinfunction "P7.1/TA0.0/S16_53") (pintype "bidirectional"))
    )
    (net (code "128") (name "unconnected-(MSP1-P7.2{slash}TA0.1{slash}S15-Pad54)") (class "Default")
      (node (ref "MSP1") (pin "54") (pinfunction "P7.2/TA0.1/S15_54") (pintype "bidirectional"))
    )
    (net (code "129") (name "unconnected-(MSP1-P7.3{slash}TA0.2{slash}S14-Pad55)") (class "Default")
      (node (ref "MSP1") (pin "55") (pinfunction "P7.3/TA0.2/S14_55") (pintype "bidirectional"))
    )
    (net (code "130") (name "unconnected-(MSP1-P7.4{slash}SMCLK{slash}S13-Pad56)") (class "Default")
      (node (ref "MSP1") (pin "56") (pinfunction "P7.4/SMCLK/S13_56") (pintype "bidirectional"))
    )
    (net (code "131") (name "unconnected-(MSP1-P7.5{slash}TA0.2{slash}S30-Pad35)") (class "Default")
      (node (ref "MSP1") (pin "35") (pinfunction "P7.5/TA0.2/S30_35") (pintype "bidirectional"))
    )
    (net (code "132") (name "unconnected-(MSP1-P7.6{slash}TA0.1{slash}S29-Pad36)") (class "Default")
      (node (ref "MSP1") (pin "36") (pinfunction "P7.6/TA0.1/S29_36") (pintype "bidirectional"))
    )
    (net (code "133") (name "unconnected-(MSP1-P7.7{slash}TA1.2{slash}TB0OUTH{slash}S27-Pad38)") (class "Default")
      (node (ref "MSP1") (pin "38") (pinfunction "P7.7/TA1.2/TB0OUTH/S27_38") (pintype "bidirectional"))
    )
    (net (code "134") (name "unconnected-(MSP1-P8.2{slash}S19-Pad46)") (class "Default")
      (node (ref "MSP1") (pin "46") (pinfunction "P8.2/S19_46") (pintype "bidirectional"))
    )
    (net (code "135") (name "unconnected-(MSP1-P8.3{slash}MCLK{slash}S18-Pad47)") (class "Default")
      (node (ref "MSP1") (pin "47") (pinfunction "P8.3/MCLK/S18_47") (pintype "bidirectional"))
    )
    (net (code "136") (name "unconnected-(MSP1-P8.4{slash}A7{slash}C7-Pad59)") (class "Default")
      (node (ref "MSP1") (pin "59") (pinfunction "P8.4/A7/C7_59") (pintype "bidirectional"))
    )
    (net (code "137") (name "unconnected-(MSP1-P8.7{slash}A4{slash}C4-Pad62)") (class "Default")
      (node (ref "MSP1") (pin "62") (pinfunction "P8.7/A4/C4_62") (pintype "bidirectional"))
    )
    (net (code "138") (name "unconnected-(MSP1-P9.0{slash}ESICH0{slash}ESITEST0{slash}A8{slash}C8-Pad67)") (class "Default")
      (node (ref "MSP1") (pin "67") (pinfunction "P9.0/ESICH0/ESITEST0/A8/C8_67") (pintype "bidirectional"))
    )
    (net (code "139") (name "unconnected-(MSP1-P9.1{slash}ESICH1{slash}ESITEST1{slash}A9{slash}C9-Pad68)") (class "Default")
      (node (ref "MSP1") (pin "68") (pinfunction "P9.1/ESICH1/ESITEST1/A9/C9_68") (pintype "bidirectional"))
    )
    (net (code "140") (name "unconnected-(MSP1-P9.2{slash}ESICH2{slash}ESITEST2{slash}A10{slash}C10-Pad69)") (class "Default")
      (node (ref "MSP1") (pin "69") (pinfunction "P9.2/ESICH2/ESITEST2/A10/C10_69") (pintype "bidirectional"))
    )
    (net (code "141") (name "unconnected-(MSP1-P9.3{slash}ESICH3{slash}ESITEST3{slash}A11{slash}C11-Pad70)") (class "Default")
      (node (ref "MSP1") (pin "70") (pinfunction "P9.3/ESICH3/ESITEST3/A11/C11_70") (pintype "bidirectional"))
    )
    (net (code "142") (name "unconnected-(MSP1-P9.4{slash}ESICI0{slash}A12{slash}C12-Pad71)") (class "Default")
      (node (ref "MSP1") (pin "71") (pinfunction "P9.4/ESICI0/A12/C12_71") (pintype "bidirectional"))
    )
    (net (code "143") (name "unconnected-(MSP1-P9.5{slash}ESICI1{slash}A13{slash}C13-Pad72)") (class "Default")
      (node (ref "MSP1") (pin "72") (pinfunction "P9.5/ESICI1/A13/C13_72") (pintype "bidirectional"))
    )
    (net (code "144") (name "unconnected-(MSP1-P9.6{slash}ESICI2{slash}A14{slash}C14-Pad73)") (class "Default")
      (node (ref "MSP1") (pin "73") (pinfunction "P9.6/ESICI2/A14/C14_73") (pintype "bidirectional"))
    )
    (net (code "145") (name "unconnected-(MSP1-P9.7{slash}ESICI3{slash}A15{slash}C15-Pad74)") (class "Default")
      (node (ref "MSP1") (pin "74") (pinfunction "P9.7/ESICI3/A15/C15_74") (pintype "bidirectional"))
    )
    (net (code "146") (name "unconnected-(MSP1-P10.0{slash}SMCLK{slash}S4-Pad95)") (class "Default")
      (node (ref "MSP1") (pin "95") (pinfunction "P10.0/SMCLK/S4_95") (pintype "bidirectional"))
    )
    (net (code "147") (name "unconnected-(MSP1-P10.1{slash}TA0.0{slash}S28-Pad37)") (class "Default")
      (node (ref "MSP1") (pin "37") (pinfunction "P10.1/TA0.0/S28_37") (pintype "bidirectional"))
    )
    (net (code "148") (name "unconnected-(MSP1-PJ.0{slash}TDO{slash}TB0OUTH{slash}SMCLK{slash}SRSCG1-Pad30)") (class "Default")
      (node (ref "MSP1") (pin "30") (pinfunction "PJ.0/TDO/TB0OUTH/SMCLK/SRSCG1_30") (pintype "bidirectional"))
    )
    (net (code "149") (name "unconnected-(MSP1-PJ.1{slash}TDI{slash}TCLK{slash}MCLK{slash}SRSCG-Pad31)") (class "Default")
      (node (ref "MSP1") (pin "31") (pinfunction "PJ.1/TDI/TCLK/MCLK/SRSCG_31") (pintype "bidirectional"))
    )
    (net (code "150") (name "unconnected-(MSP1-PJ.2{slash}TMS{slash}ACLK{slash}SROSCOFF-Pad32)") (class "Default")
      (node (ref "MSP1") (pin "32") (pinfunction "PJ.2/TMS/ACLK/SROSCOFF_32") (pintype "bidirectional"))
    )
    (net (code "151") (name "unconnected-(MSP1-PJ.3{slash}TCK{slash}COUT{slash}SRCPUOFF-Pad33)") (class "Default")
      (node (ref "MSP1") (pin "33") (pinfunction "PJ.3/TCK/COUT/SRCPUOFF_33") (pintype "bidirectional"))
    )
    (net (code "152") (name "unconnected-(MSP1-PJ.4{slash}LFXIN-Pad84)") (class "Default")
      (node (ref "MSP1") (pin "84") (pinfunction "PJ.4/LFXIN_84") (pintype "bidirectional"))
    )
    (net (code "153") (name "unconnected-(MSP1-PJ.5{slash}LFXOUT-Pad85)") (class "Default")
      (node (ref "MSP1") (pin "85") (pinfunction "PJ.5/LFXOUT_85") (pintype "bidirectional"))
    )
    (net (code "154") (name "unconnected-(MSP1-PJ.6{slash}HFXIN-Pad82)") (class "Default")
      (node (ref "MSP1") (pin "82") (pinfunction "PJ.6/HFXIN_82") (pintype "bidirectional"))
    )
    (net (code "155") (name "unconnected-(MSP1-PJ.7{slash}HFXOUT-Pad81)") (class "Default")
      (node (ref "MSP1") (pin "81") (pinfunction "PJ.7/HFXOUT_81") (pintype "bidirectional"))
    )
    (net (code "156") (name "unconnected-(MSP1-R33{slash}LCDCAP-Pad6)") (class "Default")
      (node (ref "MSP1") (pin "6") (pinfunction "R33/LCDCAP_6") (pintype "bidirectional"))
    )
    (net (code "157") (name "unconnected-(TM1-E-Pad3)") (class "Default")
      (node (ref "TM1") (pin "3") (pinfunction "E_3") (pintype "passive"))
    )
    (net (code "158") (name "unconnected-(TM2-E-Pad3)") (class "Default")
      (node (ref "TM2") (pin "3") (pinfunction "E_3") (pintype "passive"))
    )
    (net (code "159") (name "unconnected-(TM3-E-Pad3)") (class "Default")
      (node (ref "TM3") (pin "3") (pinfunction "E_3") (pintype "passive"))
    )
    (net (code "160") (name "unconnected-(TM4-E-Pad3)") (class "Default")
      (node (ref "TM4") (pin "3") (pinfunction "E_3") (pintype "passive"))
    )
    (net (code "161") (name "unconnected-(TM5-E-Pad3)") (class "Default")
      (node (ref "TM5") (pin "3") (pinfunction "E_3") (pintype "passive"))
    )
    (net (code "162") (name "unconnected-(TM6-E-Pad3)") (class "Default")
      (node (ref "TM6") (pin "3") (pinfunction "E_3") (pintype "passive"))
    )
    (net (code "163") (name "unconnected-(TM7-E-Pad3)") (class "Default")
      (node (ref "TM7") (pin "3") (pinfunction "E_3") (pintype "passive"))
    )
    (net (code "164") (name "unconnected-(TM8-E-Pad3)") (class "Default")
      (node (ref "TM8") (pin "3") (pinfunction "E_3") (pintype "passive"))
    )
    (net (code "165") (name "unconnected-(U3-AF-Pad14)") (class "Default")
      (node (ref "U3") (pin "14") (pinfunction "AF_14") (pintype "bidirectional"))
    )
    (net (code "166") (name "unconnected-(U3-FOUT{slash}IRQ-Pad11)") (class "Default")
      (node (ref "U3") (pin "11") (pinfunction "FOUT/IRQ_11") (pintype "bidirectional"))
    )
    (net (code "167") (name "unconnected-(U3-IRQ2-Pad4)") (class "Default")
      (node (ref "U3") (pin "4") (pinfunction "IRQ2_4") (pintype "bidirectional"))
    )
    (net (code "168") (name "unconnected-(U3-TIRQ-Pad12)") (class "Default")
      (node (ref "U3") (pin "12") (pinfunction "TIRQ_12") (pintype "bidirectional"))
    )
    (net (code "169") (name "unconnected-(U3-XI-Pad16)") (class "Default")
      (node (ref "U3") (pin "16") (pinfunction "XI_16") (pintype "bidirectional"))
    )
    (net (code "170") (name "unconnected-(U3-XO-Pad15)") (class "Default")
      (node (ref "U3") (pin "15") (pinfunction "XO_15") (pintype "bidirectional"))
    )
    (net (code "171") (name "unconnected-(U5-HA-Pad15)") (class "Default")
      (node (ref "U5") (pin "15") (pinfunction "HA_15") (pintype "passive"))
    )
    (net (code "172") (name "unconnected-(U5-HB-Pad12)") (class "Default")
      (node (ref "U5") (pin "12") (pinfunction "HB_12") (pintype "bidirectional"))
    )
    (net (code "173") (name "unconnected-(U8-HA-Pad15)") (class "Default")
      (node (ref "U8") (pin "15") (pinfunction "HA_15") (pintype "passive"))
    )
    (net (code "174") (name "unconnected-(U8-HB-Pad12)") (class "Default")
      (node (ref "U8") (pin "12") (pinfunction "HB_12") (pintype "bidirectional"))
    )
    (net (code "175") (name "unconnected-(U11-HA-Pad15)") (class "Default")
      (node (ref "U11") (pin "15") (pinfunction "HA_15") (pintype "passive"))
    )
    (net (code "176") (name "unconnected-(U11-HB-Pad12)") (class "Default")
      (node (ref "U11") (pin "12") (pinfunction "HB_12") (pintype "bidirectional"))
    )
    (net (code "177") (name "unconnected-(U12-HA-Pad15)") (class "Default")
      (node (ref "U12") (pin "15") (pinfunction "HA_15") (pintype "passive"))
    )
    (net (code "178") (name "unconnected-(U12-HB-Pad12)") (class "Default")
      (node (ref "U12") (pin "12") (pinfunction "HB_12") (pintype "bidirectional"))
    )
  )
)
